# BCN3D_electronics.net
KiCad netlist of a schematic drawn in EAGLE
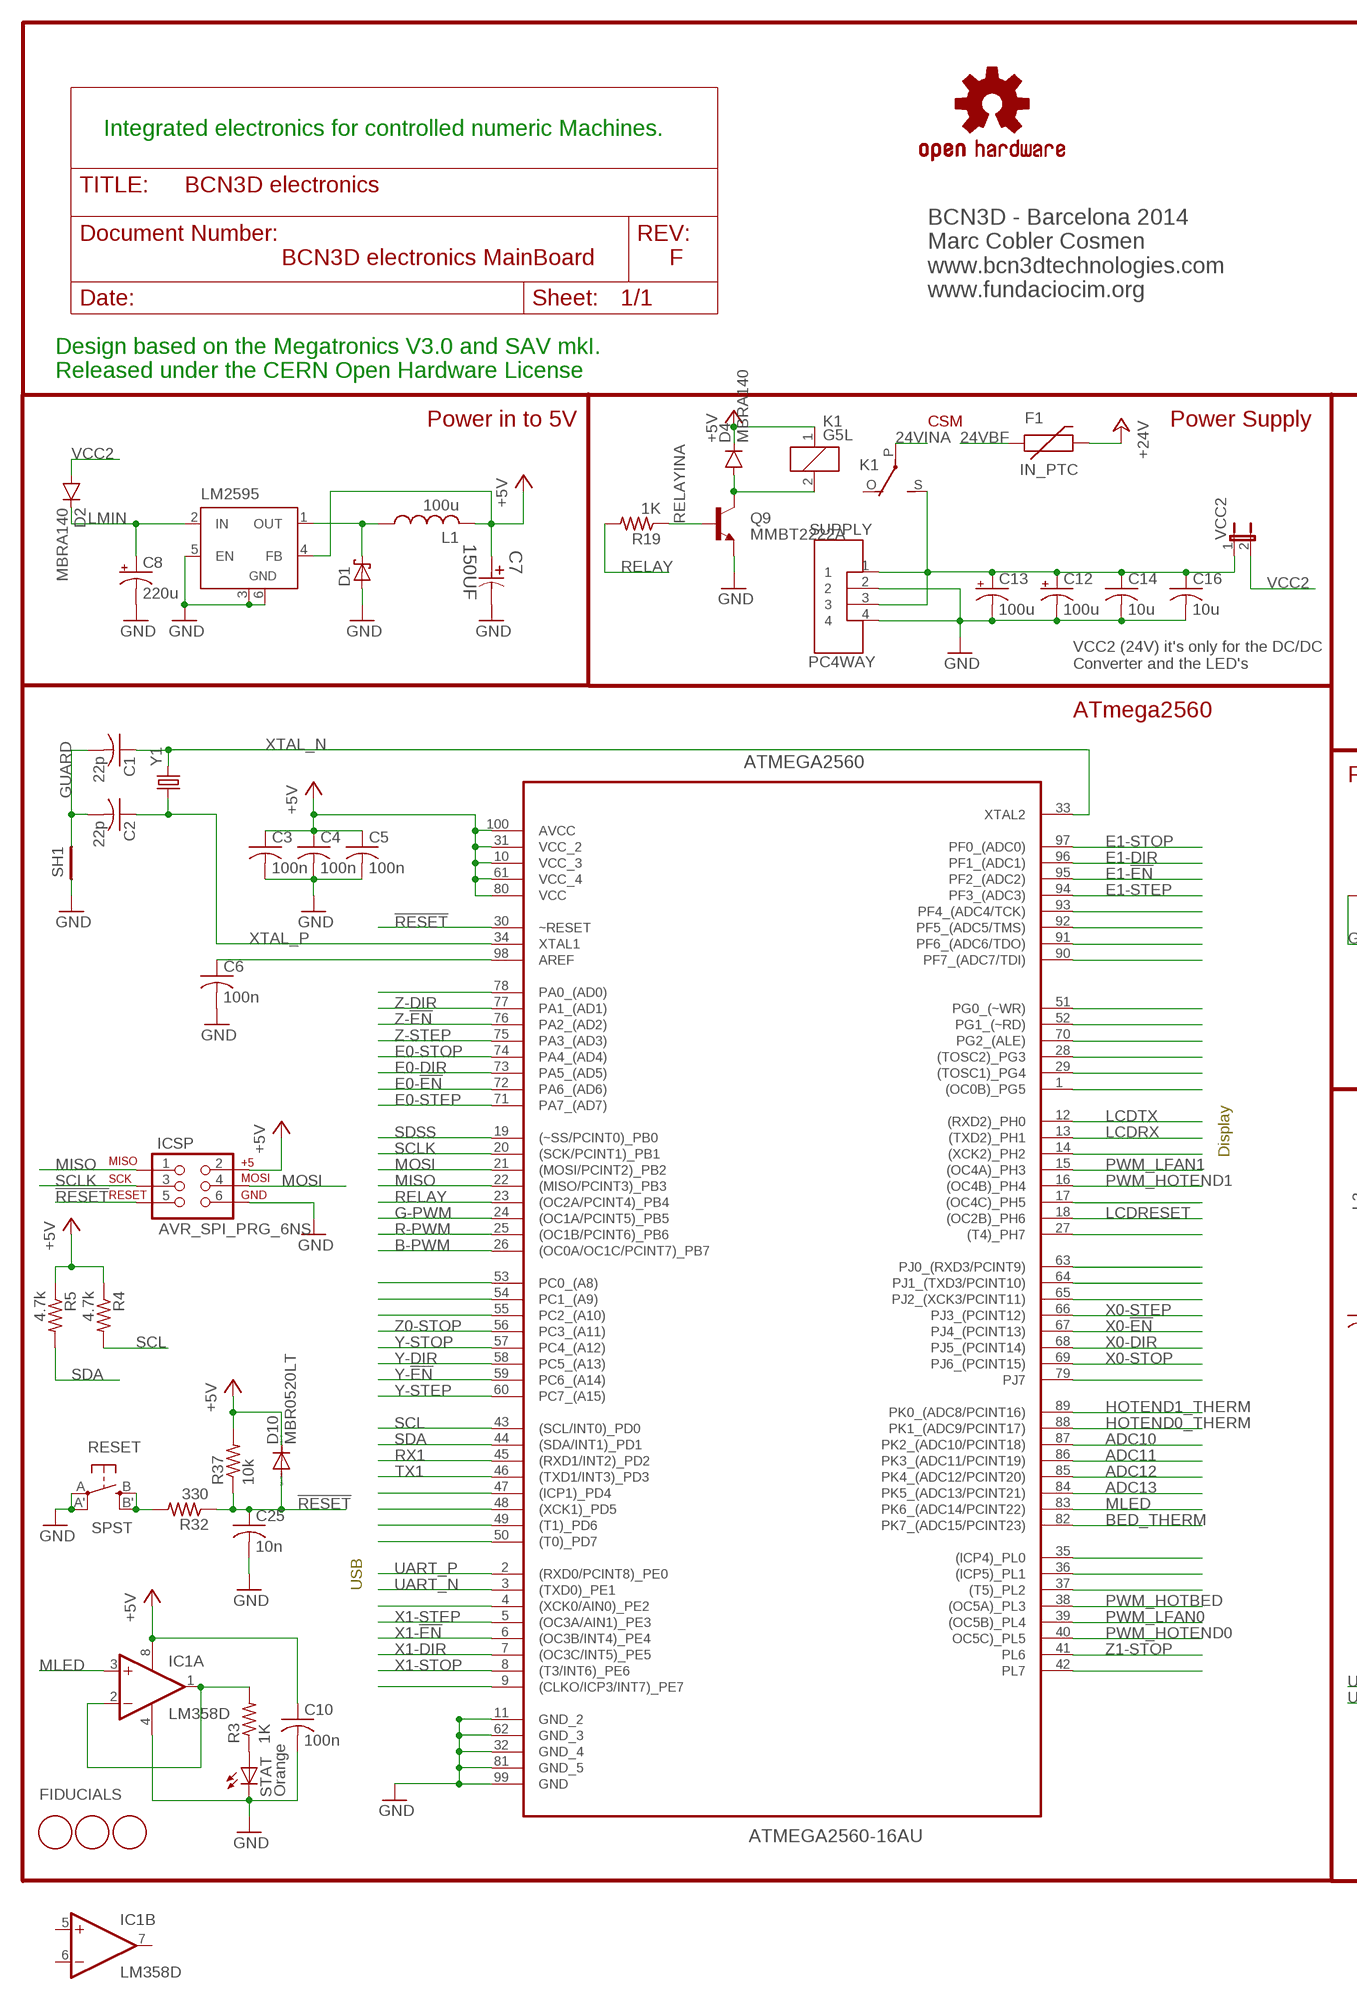
[diagram p0: schematic, sheet 1, part 1 of 2]
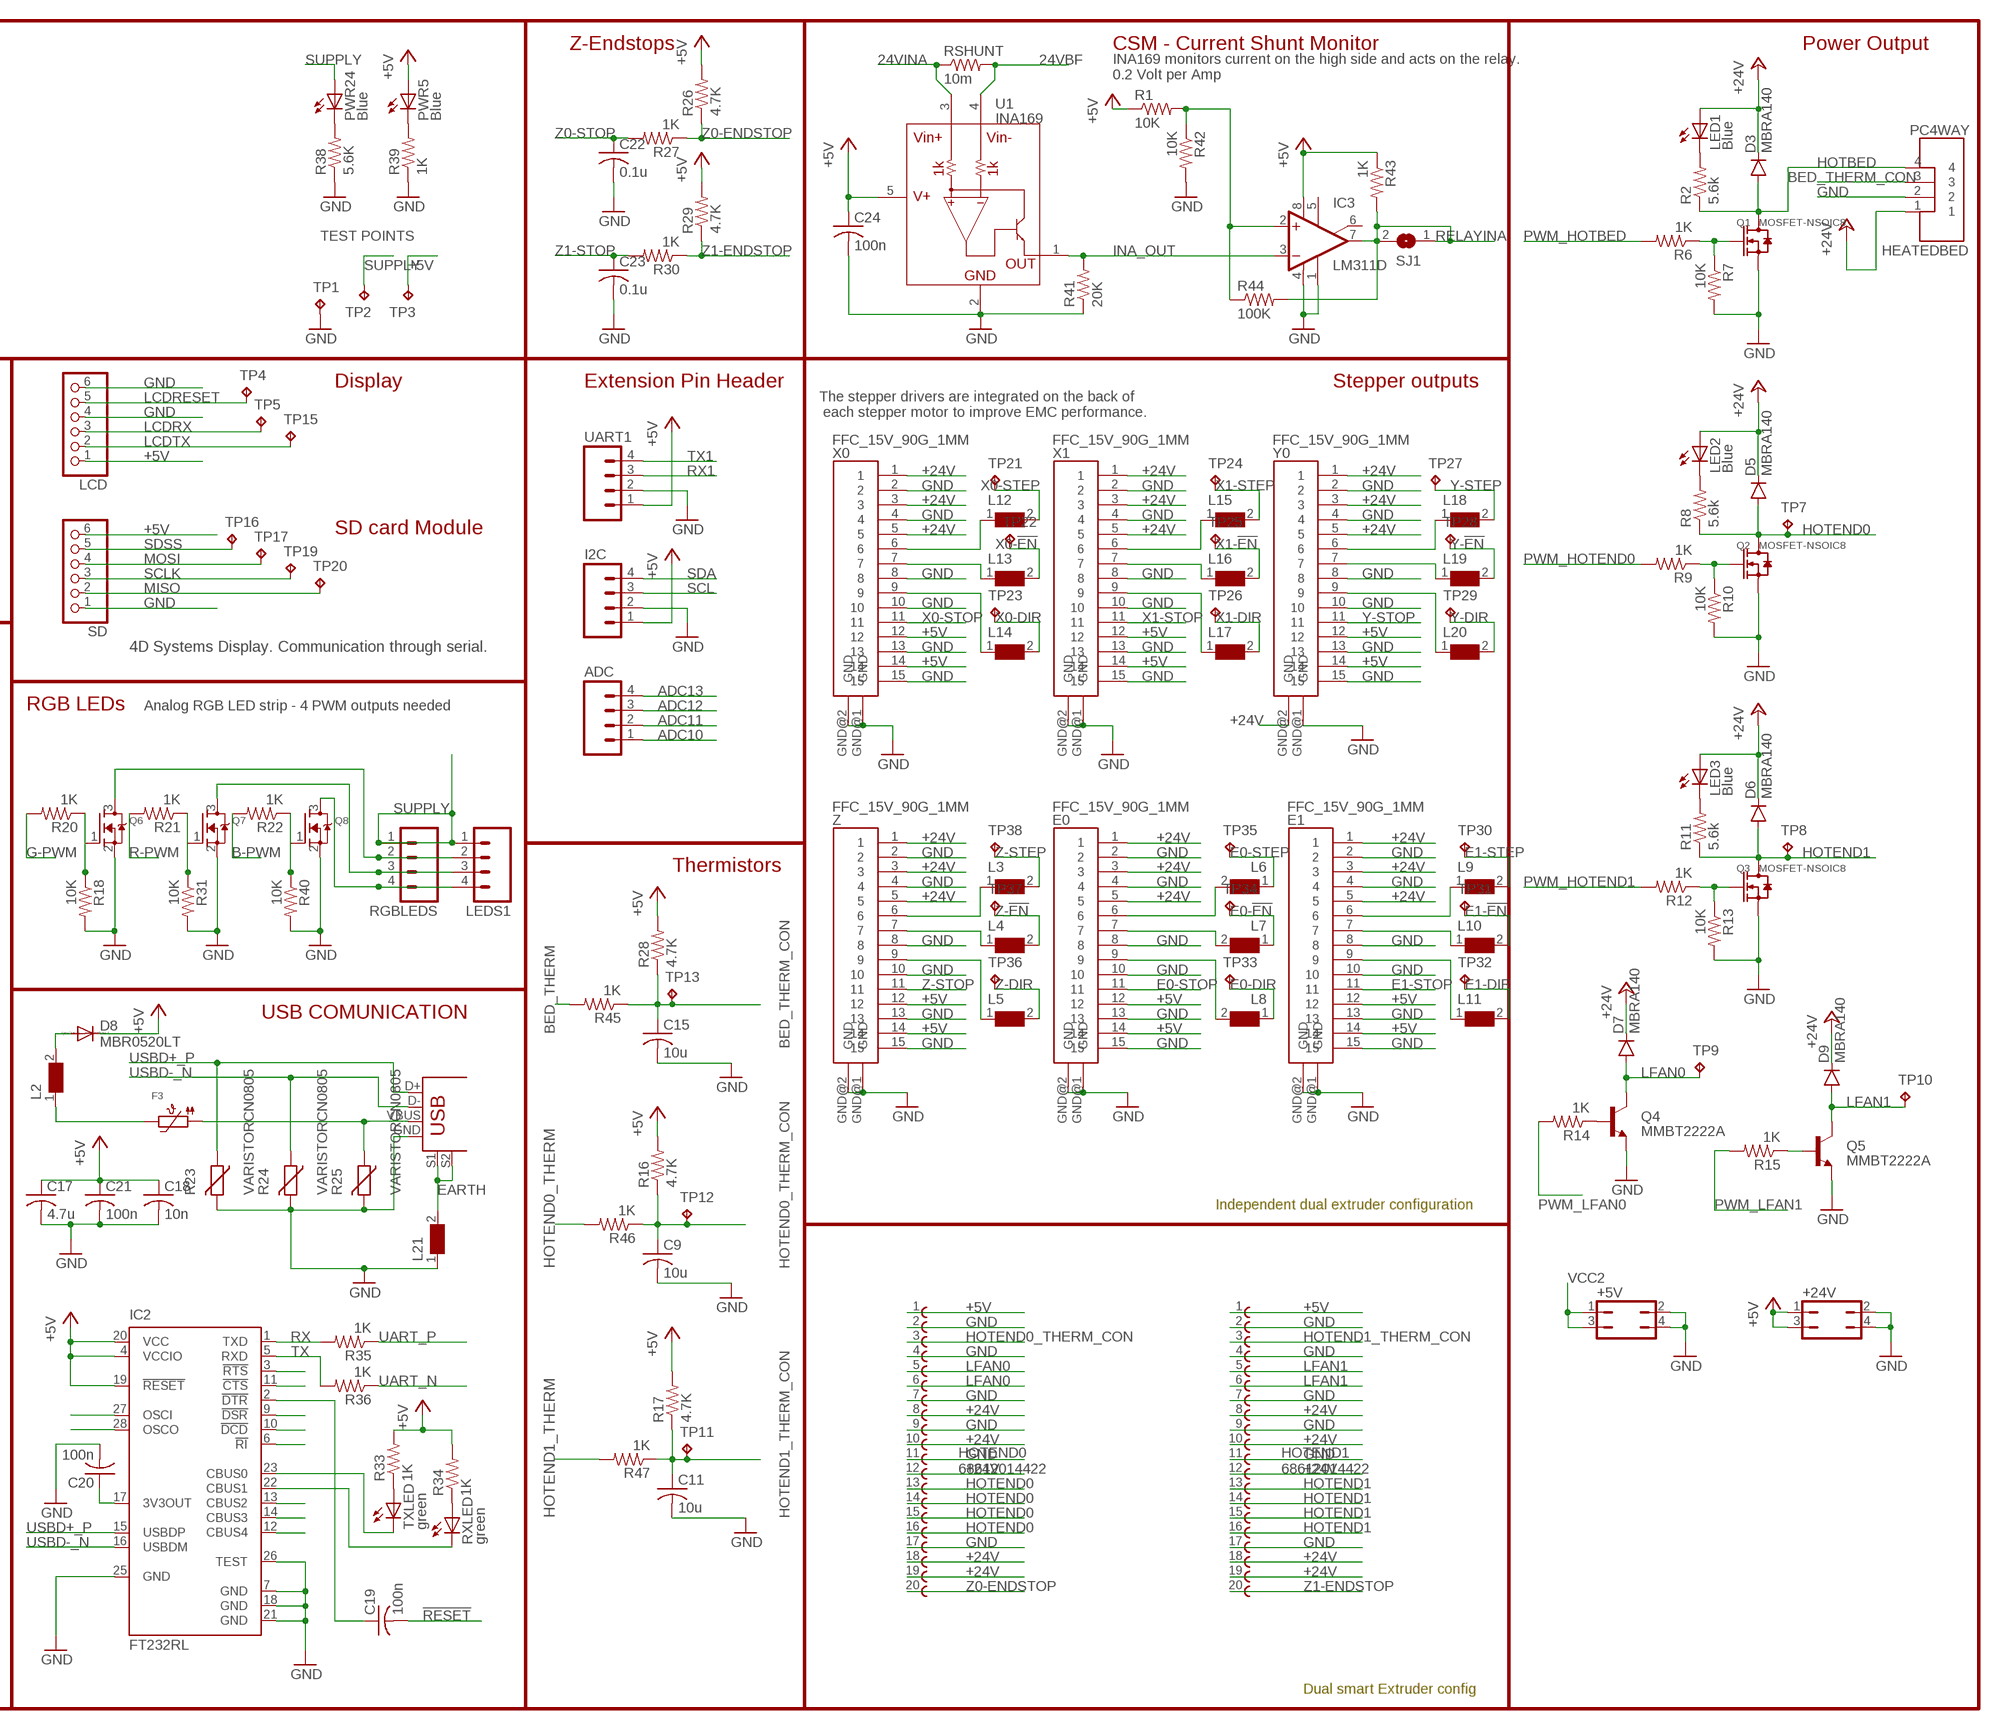
[diagram p1: schematic, sheet 1, part 2 of 2]

(export (version "E")
  (design (tool "Eeschema 10.0.6"))
  (components
    (comp (ref "+5V")
      (value "JP2Q")
      (footprint "eagle-import:JP2Q")
      (libsource (lib "eagle-import") (part "JP2Q"))
    )
    (comp (ref "+24V")
      (value "JP2Q")
      (footprint "eagle-import:JP2Q")
      (libsource (lib "eagle-import") (part "JP2Q"))
    )
    (comp (ref "ADC")
      (value "M04PTH")
      (footprint "eagle-import:1X04")
      (libsource (lib "eagle-import") (part "M04PTH"))
    )
    (comp (ref "ATMEGA2560")
      (value "ATMEGA2560-16AU")
      (footprint "eagle-import:QFP50P1600X1600X120-100N")
      (fields (field (name "MF") "ATMEL"))
      (libsource (lib "eagle-import") (part "ATMEGA2560-16AU"))
    )
    (comp (ref "C1")
      (value "22p")
      (footprint "eagle-import:C0805")
      (fields (field (name "MF") "AVX") (field (name "MPN") "08055A220KAT2A"))
      (libsource (lib "eagle-import") (part "resistor_C-USC0805"))
    )
    (comp (ref "C2")
      (value "22p")
      (footprint "eagle-import:C0805")
      (fields (field (name "MF") "AVX") (field (name "MPN") "08055A220KAT2A"))
      (libsource (lib "eagle-import") (part "resistor_C-USC0805"))
    )
    (comp (ref "C3")
      (value "100n")
      (footprint "eagle-import:C0805")
      (fields (field (name "MF") "AVX") (field (name "MPN") "08055C104KAT2A"))
      (libsource (lib "eagle-import") (part "rcl_C-USC0805"))
    )
    (comp (ref "C4")
      (value "100n")
      (footprint "eagle-import:C0805")
      (fields (field (name "MF") "AVX") (field (name "MPN") "08055C104KAT2A"))
      (libsource (lib "eagle-import") (part "rcl_C-USC0805"))
    )
    (comp (ref "C5")
      (value "100n")
      (footprint "eagle-import:C0805")
      (fields (field (name "MF") "AVX") (field (name "MPN") "08055C104KAT2A"))
      (libsource (lib "eagle-import") (part "rcl_C-USC0805"))
    )
    (comp (ref "C6")
      (value "100n")
      (footprint "eagle-import:C0805")
      (fields (field (name "MF") "AVX") (field (name "MPN") "08055C104KAT2A"))
      (libsource (lib "eagle-import") (part "rcl_C-USC0805"))
    )
    (comp (ref "C7")
      (value "150UF")
      (footprint "eagle-import:CAPAE660X610N")
      (fields
        (field (name "MPN") "EEE-FK0J221P")
        (field (name "TOLERANCE") "±20 %")
        (field (name "MF") "PANASONIC ELECTRONIC COMPONENTS")
        (field (name "MPN_1") "EEEFP1A151AP")
        (field (name "OC_FARNELL") "1539463")
      )
      (libsource (lib "eagle-import") (part "EEE--CASE-DFK0J221P"))
    )
    (comp (ref "C8")
      (value "220u")
      (footprint "eagle-import:UD-8X10_NICHICON")
      (fields (field (name "MF") "PANASONIC ELECTRONIC COMPONENTS") (field (name "MPN") "EEE1VA221UAP"))
      (libsource (lib "eagle-import") (part "CPOL-USUD-8X10"))
    )
    (comp (ref "C9")
      (value "10u")
      (footprint "eagle-import:C0805")
      (fields (field (name "MF") "AVX") (field (name "MPN") "08055C104KAT2A"))
      (libsource (lib "eagle-import") (part "rcl_C-USC0805"))
    )
    (comp (ref "C10")
      (value "100n")
      (footprint "eagle-import:C0805")
      (fields (field (name "MF") "AVX") (field (name "MPN") "08055C104KAT2A"))
      (libsource (lib "eagle-import") (part "rcl_C-USC0805"))
    )
    (comp (ref "C11")
      (value "10u")
      (footprint "eagle-import:C0805")
      (fields (field (name "MF") "AVX") (field (name "MPN") "08055C104KAT2A"))
      (libsource (lib "eagle-import") (part "rcl_C-USC0805"))
    )
    (comp (ref "C12")
      (value "100u")
      (footprint "eagle-import:UD-8X10_NICHICON")
      (fields (field (name "MF") "PANASONIC ELECTRONIC COMPONENTS") (field (name "MPN") "EEEFC1V101AP"))
      (libsource (lib "eagle-import") (part "CPOL-USUD-8X10"))
    )
    (comp (ref "C13")
      (value "100u")
      (footprint "eagle-import:UD-8X10_NICHICON")
      (fields (field (name "MF") "PANASONIC ELECTRONIC COMPONENTS") (field (name "MPN") "EEEFC1V101AP"))
      (libsource (lib "eagle-import") (part "CPOL-USUD-8X10"))
    )
    (comp (ref "C14")
      (value "10u")
      (footprint "eagle-import:C1210K")
      (fields (field (name "MF") "MURATA") (field (name "MPN") "GRM32ER7YA106KA12L"))
      (libsource (lib "eagle-import") (part "rcl_C-USC1210K"))
    )
    (comp (ref "C15")
      (value "10u")
      (footprint "eagle-import:C0805")
      (fields (field (name "MF") "AVX") (field (name "MPN") "08055C104KAT2A"))
      (libsource (lib "eagle-import") (part "rcl_C-USC0805"))
    )
    (comp (ref "C16")
      (value "10u")
      (footprint "eagle-import:C1210K")
      (fields (field (name "MF") "MURATA") (field (name "MPN") "GRM32ER7YA106KA12L"))
      (libsource (lib "eagle-import") (part "rcl_C-USC1210K"))
    )
    (comp (ref "C17")
      (value "4.7u")
      (footprint "eagle-import:C0805")
      (fields (field (name "MF") "AVX") (field (name "MPN") "06035C103JAT2A"))
      (libsource (lib "eagle-import") (part "C-USC0805"))
    )
    (comp (ref "C18")
      (value "10n")
      (footprint "eagle-import:C0805")
      (fields (field (name "MF") "AVX") (field (name "MPN") "08055C103KAT2A"))
      (libsource (lib "eagle-import") (part "C-USC0805"))
    )
    (comp (ref "C19")
      (value "100n")
      (footprint "eagle-import:C0805")
      (fields (field (name "MF") "AVX") (field (name "MPN") "08055C104KAT2A"))
      (libsource (lib "eagle-import") (part "rcl_C-USC0805"))
    )
    (comp (ref "C20")
      (value "100n")
      (footprint "eagle-import:C0805")
      (fields (field (name "MF") "AVX") (field (name "MPN") "08055C104KAT2A"))
      (libsource (lib "eagle-import") (part "rcl_C-USC0805"))
    )
    (comp (ref "C21")
      (value "100n")
      (footprint "eagle-import:C0805")
      (fields (field (name "MF") "AVX") (field (name "MPN") "08055C104KAT2A"))
      (libsource (lib "eagle-import") (part "C-USC0805"))
    )
    (comp (ref "C22")
      (value "0.1u")
      (footprint "eagle-import:C0805")
      (fields (field (name "MF") "AVX") (field (name "MPN") "08055C104KAT2A"))
      (libsource (lib "eagle-import") (part "rcl_C-USC0805"))
    )
    (comp (ref "C23")
      (value "0.1u")
      (footprint "eagle-import:C0805")
      (fields (field (name "MF") "AVX") (field (name "MPN") "08055C104KAT2A"))
      (libsource (lib "eagle-import") (part "rcl_C-USC0805"))
    )
    (comp (ref "C24")
      (value "100n")
      (footprint "eagle-import:C0805")
      (fields (field (name "MF") "AVX") (field (name "MPN") "08055C104KAT2A"))
      (libsource (lib "eagle-import") (part "C-USC0805"))
    )
    (comp (ref "C25")
      (value "10n")
      (footprint "eagle-import:C0805")
      (fields (field (name "MF") "AVX") (field (name "MPN") "08055C103KAT2A"))
      (libsource (lib "eagle-import") (part "rcl_C-USC0805"))
    )
    (comp (ref "D1")
      (value "SCHOTTKY-DIODESMC")
      (footprint "eagle-import:SMC")
      (fields (field (name "MF") "ON SEMICONDUCTOR") (field (name "MPN") "MBRS340T3G"))
      (libsource (lib "eagle-import") (part "SCHOTTKY-DIODESMC"))
    )
    (comp (ref "D2")
      (value "MBRA140")
      (footprint "eagle-import:SMA-DIODE")
      (fields (field (name "MF") "DIODES INC.") (field (name "MPN") "B140-13-F"))
      (libsource (lib "eagle-import") (part "DIODESMA"))
    )
    (comp (ref "D3")
      (value "MBRA140")
      (footprint "eagle-import:SMA-DIODE")
      (fields (field (name "MF") "DIODES INC.") (field (name "MPN") "B140-13-F"))
      (libsource (lib "eagle-import") (part "DIODESMA"))
    )
    (comp (ref "D4")
      (value "MBRA140")
      (footprint "eagle-import:SMA-DIODE")
      (fields (field (name "MF") "DIODES INC.") (field (name "MPN") "B140-13-F"))
      (libsource (lib "eagle-import") (part "DIODESMA"))
    )
    (comp (ref "D5")
      (value "MBRA140")
      (footprint "eagle-import:SMA-DIODE")
      (fields (field (name "MF") "DIODES INC.") (field (name "MPN") "B140-13-F"))
      (libsource (lib "eagle-import") (part "DIODESMA"))
    )
    (comp (ref "D6")
      (value "MBRA140")
      (footprint "eagle-import:SMA-DIODE")
      (fields (field (name "MF") "DIODES INC.") (field (name "MPN") "B140-13-F"))
      (libsource (lib "eagle-import") (part "DIODESMA"))
    )
    (comp (ref "D7")
      (value "MBRA140")
      (footprint "eagle-import:SMA-DIODE")
      (fields (field (name "MF") "DIODES INC.") (field (name "MPN") "B140-13-F"))
      (libsource (lib "eagle-import") (part "DIODESMA"))
    )
    (comp (ref "D8")
      (value "MBR0520LT")
      (footprint "eagle-import:SOD123")
      (fields (field (name "MF") "PANASONIC ELECTRONIC COMPONENTS") (field (name "MPN") "DA22F2100L"))
      (libsource (lib "eagle-import") (part "MBR0520LT"))
    )
    (comp (ref "D9")
      (value "MBRA140")
      (footprint "eagle-import:SMA-DIODE")
      (fields (field (name "MF") "DIODES INC.") (field (name "MPN") "B140-13-F"))
      (libsource (lib "eagle-import") (part "DIODESMA"))
    )
    (comp (ref "D10")
      (value "MBR0520LT")
      (footprint "eagle-import:SOD123")
      (fields (field (name "MF") "PANASONIC ELECTRONIC COMPONENTS") (field (name "MPN") "DA22F2100L"))
      (libsource (lib "eagle-import") (part "MBR0520LT"))
    )
    (comp (ref "E0")
      (value "FFC_15V_90G_1MM")
      (footprint "eagle-import:TE_FFC_CON1MM")
      (libsource (lib "eagle-import") (part "FFC_15V_90G_1MM"))
    )
    (comp (ref "E1")
      (value "FFC_15V_90G_1MM")
      (footprint "eagle-import:TE_FFC_CON1MM")
      (libsource (lib "eagle-import") (part "FFC_15V_90G_1MM"))
    )
    (comp (ref "F1")
      (value "IN_PTC")
      (footprint "eagle-import:PTC-1206")
      (fields (field (name "MF") "SCHURTER") (field (name "MPN") "3413.0329.22"))
      (libsource (lib "eagle-import") (part "PTCSMD"))
    )
    (comp (ref "F3")
      (value "MICROBUILDER_PTC1206_L")
      (footprint "eagle-import:MICROBUILDER_1206_PTC")
      (fields (field (name "MF") "LITTELFUSE") (field (name "MPN") "1206L050YR"))
      (libsource (lib "eagle-import") (part "MICROBUILDER_PTC1206_L"))
    )
    (comp (ref "FID1")
      (value "FIDUCIAL")
      (footprint "eagle-import:FIDUCIAL_1MM")
      (libsource (lib "eagle-import") (part "FIDUCIAL"))
    )
    (comp (ref "FID2")
      (value "FIDUCIAL")
      (footprint "eagle-import:FIDUCIAL_1MM")
      (libsource (lib "eagle-import") (part "FIDUCIAL"))
    )
    (comp (ref "FID3")
      (value "FIDUCIAL")
      (footprint "eagle-import:FIDUCIAL_1MM")
      (libsource (lib "eagle-import") (part "FIDUCIAL"))
    )
    (comp (ref "HEATEDBED")
      (value "PC4WAY")
      (footprint "eagle-import:MOLEX_MINIFIT-JR")
      (fields (field (name "MF") "MOLEX") (field (name "MPN") "39303045"))
      (libsource (lib "eagle-import") (part "POWER_CONNECTOR_4WAY"))
    )
    (comp (ref "HOTEND0")
      (value "68612014422")
      (footprint "eagle-import:68612014422")
      (libsource (lib "eagle-import") (part "68612014422"))
    )
    (comp (ref "HOTEND1")
      (value "68612014422")
      (footprint "eagle-import:68612014422")
      (libsource (lib "eagle-import") (part "68612014422"))
    )
    (comp (ref "I2C")
      (value "M04PTH")
      (footprint "eagle-import:1X04")
      (libsource (lib "eagle-import") (part "M04PTH"))
    )
    (comp (ref "IC1")
      (value "LM358D")
      (footprint "eagle-import:SO08")
      (fields
        (field (name "MF") "STMICROELECTRONICS")
        (field (name "MPN") "LM2904DT")
        (field (name "OC_FARNELL") "1564327")
      )
      (libsource (lib "eagle-import") (part "LM358D"))
    )
    (comp (ref "IC2")
      (value "FT232RL")
      (footprint "eagle-import:SSOP28")
      (fields (field (name "MF") "FTDI"))
      (libsource (lib "eagle-import") (part "FT232RL"))
    )
    (comp (ref "IC3")
      (value "LM311D")
      (footprint "eagle-import:SO08")
      (libsource (lib "eagle-import") (part "LM311D"))
    )
    (comp (ref "ICSP")
      (value "AVR_SPI_PRG_6NS")
      (footprint "eagle-import:2X3-NS")
      (libsource (lib "eagle-import") (part "AVR_SPI_PRG_6NS"))
    )
    (comp (ref "K1")
      (value "G5L")
      (footprint "eagle-import:G5LE")
      (fields
        (field (name "MF") "OMRON ELECTRONIC COMPONENTS")
        (field (name "MPN") "G5LA-1 5DC")
        (field (name "OC_FARNELL") "1455502")
      )
      (libsource (lib "eagle-import") (part "G5L"))
    )
    (comp (ref "L1")
      (value "100u")
      (footprint "eagle-import:SSR1260")
      (fields (field (name "MF") "BOURNS") (field (name "MPN") "SRR1260-101M"))
      (libsource (lib "eagle-import") (part "INDUCTANCE"))
    )
    (comp (ref "L2")
      (value "WE-CBF_0805")
      (footprint "eagle-import:0805")
      (libsource (lib "eagle-import") (part "WE-CBF_0805"))
    )
    (comp (ref "L3")
      (value "WE-CBF_0805")
      (footprint "eagle-import:0805")
      (libsource (lib "eagle-import") (part "WE-CBF_0805"))
    )
    (comp (ref "L4")
      (value "WE-CBF_0805")
      (footprint "eagle-import:0805")
      (libsource (lib "eagle-import") (part "WE-CBF_0805"))
    )
    (comp (ref "L5")
      (value "WE-CBF_0805")
      (footprint "eagle-import:0805")
      (libsource (lib "eagle-import") (part "WE-CBF_0805"))
    )
    (comp (ref "L6")
      (value "WE-CBF_0805")
      (footprint "eagle-import:0805")
      (libsource (lib "eagle-import") (part "WE-CBF_0805"))
    )
    (comp (ref "L7")
      (value "WE-CBF_0805")
      (footprint "eagle-import:0805")
      (libsource (lib "eagle-import") (part "WE-CBF_0805"))
    )
    (comp (ref "L8")
      (value "WE-CBF_0805")
      (footprint "eagle-import:0805")
      (libsource (lib "eagle-import") (part "WE-CBF_0805"))
    )
    (comp (ref "L9")
      (value "WE-CBF_0805")
      (footprint "eagle-import:0805")
      (libsource (lib "eagle-import") (part "WE-CBF_0805"))
    )
    (comp (ref "L10")
      (value "WE-CBF_0805")
      (footprint "eagle-import:0805")
      (libsource (lib "eagle-import") (part "WE-CBF_0805"))
    )
    (comp (ref "L11")
      (value "WE-CBF_0805")
      (footprint "eagle-import:0805")
      (libsource (lib "eagle-import") (part "WE-CBF_0805"))
    )
    (comp (ref "L12")
      (value "WE-CBF_0805")
      (footprint "eagle-import:0805")
      (libsource (lib "eagle-import") (part "WE-CBF_0805"))
    )
    (comp (ref "L13")
      (value "WE-CBF_0805")
      (footprint "eagle-import:0805")
      (libsource (lib "eagle-import") (part "WE-CBF_0805"))
    )
    (comp (ref "L14")
      (value "WE-CBF_0805")
      (footprint "eagle-import:0805")
      (libsource (lib "eagle-import") (part "WE-CBF_0805"))
    )
    (comp (ref "L15")
      (value "WE-CBF_0805")
      (footprint "eagle-import:0805")
      (libsource (lib "eagle-import") (part "WE-CBF_0805"))
    )
    (comp (ref "L16")
      (value "WE-CBF_0805")
      (footprint "eagle-import:0805")
      (libsource (lib "eagle-import") (part "WE-CBF_0805"))
    )
    (comp (ref "L17")
      (value "WE-CBF_0805")
      (footprint "eagle-import:0805")
      (libsource (lib "eagle-import") (part "WE-CBF_0805"))
    )
    (comp (ref "L18")
      (value "WE-CBF_0805")
      (footprint "eagle-import:0805")
      (libsource (lib "eagle-import") (part "WE-CBF_0805"))
    )
    (comp (ref "L19")
      (value "WE-CBF_0805")
      (footprint "eagle-import:0805")
      (libsource (lib "eagle-import") (part "WE-CBF_0805"))
    )
    (comp (ref "L20")
      (value "WE-CBF_0805")
      (footprint "eagle-import:0805")
      (libsource (lib "eagle-import") (part "WE-CBF_0805"))
    )
    (comp (ref "L21")
      (value "WE-CBF_0805")
      (footprint "eagle-import:0805")
      (libsource (lib "eagle-import") (part "WE-CBF_0805"))
    )
    (comp (ref "LCD")
      (value "PINHD-1X6")
      (footprint "eagle-import:1X06")
      (libsource (lib "eagle-import") (part "PINHD-1X6"))
    )
    (comp (ref "LED1")
      (value "Blue")
      (footprint "eagle-import:CHIPLED_0805")
      (fields (field (name "MF") "MULTICOMP") (field (name "MPN") "OVS-0803"))
      (libsource (lib "eagle-import") (part "led_LEDCHIPLED_0805"))
    )
    (comp (ref "LED2")
      (value "Blue")
      (footprint "eagle-import:CHIPLED_0805")
      (fields (field (name "MF") "MULTICOMP") (field (name "MPN") "OVS-0803"))
      (libsource (lib "eagle-import") (part "led_LEDCHIPLED_0805"))
    )
    (comp (ref "LED3")
      (value "Blue")
      (footprint "eagle-import:CHIPLED_0805")
      (fields (field (name "MF") "MULTICOMP") (field (name "MPN") "OVS-0803"))
      (libsource (lib "eagle-import") (part "led_LEDCHIPLED_0805"))
    )
    (comp (ref "LEDS1")
      (value "M04PTH")
      (footprint "eagle-import:1X04")
      (libsource (lib "eagle-import") (part "M04PTH"))
    )
    (comp (ref "LM2595")
      (value "LM2595")
      (footprint "eagle-import:TO263-5")
      (fields (field (name "MF") "TEXAS INSTRUMENTS") (field (name "MPN") "LM2595S-5.0/NOPB"))
      (libsource (lib "eagle-import") (part "LM2595"))
    )
    (comp (ref "LOGO1")
      (value "OSHW-LOGOM")
      (footprint "eagle-import:OSHW-LOGO-M")
      (libsource (lib "eagle-import") (part "OSHW-LOGOM"))
    )
    (comp (ref "PWR5")
      (value "Blue")
      (footprint "eagle-import:CHIPLED_0805")
      (fields (field (name "MF") "MULTICOMP") (field (name "MPN") "OVS-0803"))
      (libsource (lib "eagle-import") (part "led_LEDCHIPLED_0805"))
    )
    (comp (ref "PWR24")
      (value "Blue")
      (footprint "eagle-import:CHIPLED_0805")
      (fields (field (name "MF") "MULTICOMP") (field (name "MPN") "OVS-0803"))
      (libsource (lib "eagle-import") (part "led_LEDCHIPLED_0805"))
    )
    (comp (ref "Q1")
      (value "MOSFET-NSOIC8")
      (footprint "eagle-import:SOIC8")
      (fields (field (name "MF") "INTERNATIONAL RECTIFIER") (field (name "MPN") "IRF8736PBF"))
      (libsource (lib "eagle-import") (part "MOSFET-NSOIC8"))
    )
    (comp (ref "Q2")
      (value "MOSFET-NSOIC8")
      (footprint "eagle-import:SOIC8")
      (fields (field (name "MF") "INTERNATIONAL RECTIFIER") (field (name "MPN") "IRF8736PBF"))
      (libsource (lib "eagle-import") (part "MOSFET-NSOIC8"))
    )
    (comp (ref "Q3")
      (value "MOSFET-NSOIC8")
      (footprint "eagle-import:SOIC8")
      (fields (field (name "MF") "INTERNATIONAL RECTIFIER") (field (name "MPN") "IRF8736PBF"))
      (libsource (lib "eagle-import") (part "MOSFET-NSOIC8"))
    )
    (comp (ref "Q4")
      (value "MMBT2222A")
      (footprint "eagle-import:SOT23-3")
      (fields (field (name "MF") "NXP") (field (name "MPN") "BC817-40"))
      (libsource (lib "eagle-import") (part "TRANSISTOR_NPNMMBT2222A"))
    )
    (comp (ref "Q5")
      (value "MMBT2222A")
      (footprint "eagle-import:SOT23-3")
      (fields (field (name "MF") "NXP") (field (name "MPN") "BC817-40"))
      (libsource (lib "eagle-import") (part "TRANSISTOR_NPNMMBT2222A"))
    )
    (comp (ref "Q6")
      (value "MOSFET-NREFLOW")
      (footprint "eagle-import:SOT23")
      (fields (field (name "MF") "NXP") (field (name "MPN") "BSH103,215"))
      (libsource (lib "eagle-import") (part "MOSFET-NREFLOW"))
    )
    (comp (ref "Q7")
      (value "MOSFET-NREFLOW")
      (footprint "eagle-import:SOT23")
      (fields (field (name "MF") "NXP") (field (name "MPN") "BSH103,215"))
      (libsource (lib "eagle-import") (part "MOSFET-NREFLOW"))
    )
    (comp (ref "Q8")
      (value "MOSFET-NREFLOW")
      (footprint "eagle-import:SOT23")
      (fields (field (name "MF") "NXP") (field (name "MPN") "BSH103,215"))
      (libsource (lib "eagle-import") (part "MOSFET-NREFLOW"))
    )
    (comp (ref "Q9")
      (value "MMBT2222A")
      (footprint "eagle-import:SOT23-3")
      (fields (field (name "MF") "NXP") (field (name "MPN") "BC817-40"))
      (libsource (lib "eagle-import") (part "TRANSISTOR_NPNMMBT2222A"))
    )
    (comp (ref "R1")
      (value "10K")
      (footprint "eagle-import:M0805")
      (fields (field (name "MF") "BOURNS") (field (name "MPN") "CR0805-JW-102ELF"))
      (libsource (lib "eagle-import") (part "rcl_R-US_M0805"))
    )
    (comp (ref "R2")
      (value "5.6k")
      (footprint "eagle-import:M0805")
      (fields (field (name "MF") "BOURNS") (field (name "MPN") "CR0805-JW-102ELF"))
      (libsource (lib "eagle-import") (part "rcl_R-US_M0805"))
    )
    (comp (ref "R3")
      (value "1K")
      (footprint "eagle-import:R0805")
      (fields (field (name "MF") "BOURNS") (field (name "MPN") "CR0805-JW-102ELF"))
      (libsource (lib "eagle-import") (part "rcl_R-US_R0805"))
    )
    (comp (ref "R4")
      (value "4.7k")
      (footprint "eagle-import:M0805")
      (fields (field (name "MF") "BOURNS") (field (name "MPN") "CR0805-JW-103ELF"))
      (libsource (lib "eagle-import") (part "rcl_R-US_M0805"))
    )
    (comp (ref "R5")
      (value "4.7k")
      (footprint "eagle-import:M0805")
      (fields (field (name "MF") "BOURNS") (field (name "MPN") "CR0805-JW-103ELF"))
      (libsource (lib "eagle-import") (part "rcl_R-US_M0805"))
    )
    (comp (ref "R6")
      (value "1K")
      (footprint "eagle-import:M0805")
      (fields (field (name "MF") "BOURNS") (field (name "MPN") "CR0805-JW-102ELF"))
      (libsource (lib "eagle-import") (part "rcl_R-US_M0805"))
    )
    (comp (ref "R7")
      (value "10K")
      (footprint "eagle-import:M0805")
      (fields (field (name "MF") "BOURNS") (field (name "MPN") "CR0805-JW-103ELF"))
      (libsource (lib "eagle-import") (part "rcl_R-US_M0805"))
    )
    (comp (ref "R8")
      (value "5.6k")
      (footprint "eagle-import:M0805")
      (fields (field (name "MF") "BOURNS") (field (name "MPN") "CR0805-JW-102ELF"))
      (libsource (lib "eagle-import") (part "rcl_R-US_M0805"))
    )
    (comp (ref "R9")
      (value "1K")
      (footprint "eagle-import:M0805")
      (fields (field (name "MF") "BOURNS") (field (name "MPN") "CR0805-JW-102ELF"))
      (libsource (lib "eagle-import") (part "rcl_R-US_M0805"))
    )
    (comp (ref "R10")
      (value "10K")
      (footprint "eagle-import:M0805")
      (fields (field (name "MF") "BOURNS") (field (name "MPN") "CR0805-JW-103ELF"))
      (libsource (lib "eagle-import") (part "rcl_R-US_M0805"))
    )
    (comp (ref "R11")
      (value "5.6k")
      (footprint "eagle-import:M0805")
      (fields (field (name "MF") "BOURNS") (field (name "MPN") "CR0805-JW-102ELF"))
      (libsource (lib "eagle-import") (part "rcl_R-US_M0805"))
    )
    (comp (ref "R12")
      (value "1K")
      (footprint "eagle-import:M0805")
      (fields (field (name "MF") "BOURNS") (field (name "MPN") "CR0805-JW-102ELF"))
      (libsource (lib "eagle-import") (part "rcl_R-US_M0805"))
    )
    (comp (ref "R13")
      (value "10K")
      (footprint "eagle-import:M0805")
      (fields (field (name "MF") "BOURNS") (field (name "MPN") "CR0805-JW-103ELF"))
      (libsource (lib "eagle-import") (part "rcl_R-US_M0805"))
    )
    (comp (ref "R14")
      (value "1K")
      (footprint "eagle-import:M0805")
      (fields (field (name "MF") "BOURNS") (field (name "MPN") "CR0805-JW-102ELF"))
      (libsource (lib "eagle-import") (part "rcl_R-US_M0805"))
    )
    (comp (ref "R15")
      (value "1K")
      (footprint "eagle-import:M0805")
      (fields (field (name "MF") "BOURNS") (field (name "MPN") "CR0805-JW-102ELF"))
      (libsource (lib "eagle-import") (part "rcl_R-US_M0805"))
    )
    (comp (ref "R16")
      (value "4.7K")
      (footprint "eagle-import:M0805")
      (fields (field (name "MF") "BOURNS") (field (name "MPN") "CR0805-FX-4701GLF"))
      (libsource (lib "eagle-import") (part "rcl_R-US_M0805"))
    )
    (comp (ref "R17")
      (value "4.7K")
      (footprint "eagle-import:M0805")
      (fields (field (name "MF") "BOURNS") (field (name "MPN") "CR0805-FX-4701GLF"))
      (libsource (lib "eagle-import") (part "rcl_R-US_M0805"))
    )
    (comp (ref "R18")
      (value "10K")
      (footprint "eagle-import:M0805")
      (fields (field (name "MF") "BOURNS") (field (name "MPN") "CR0805-JW-102ELF"))
      (libsource (lib "eagle-import") (part "rcl_R-US_M0805"))
    )
    (comp (ref "R19")
      (value "1K")
      (footprint "eagle-import:M0805")
      (fields (field (name "MF") "BOURNS") (field (name "MPN") "CR0805-JW-102ELF"))
      (libsource (lib "eagle-import") (part "rcl_R-US_M0805"))
    )
    (comp (ref "R20")
      (value "1K")
      (footprint "eagle-import:M0805")
      (fields (field (name "MF") "BOURNS") (field (name "MPN") "CR0805-JW-102ELF"))
      (libsource (lib "eagle-import") (part "rcl_R-US_M0805"))
    )
    (comp (ref "R21")
      (value "1K")
      (footprint "eagle-import:M0805")
      (fields (field (name "MF") "BOURNS") (field (name "MPN") "CR0805-JW-102ELF"))
      (libsource (lib "eagle-import") (part "rcl_R-US_M0805"))
    )
    (comp (ref "R22")
      (value "1K")
      (footprint "eagle-import:M0805")
      (fields (field (name "MF") "BOURNS") (field (name "MPN") "CR0805-JW-102ELF"))
      (libsource (lib "eagle-import") (part "rcl_R-US_M0805"))
    )
    (comp (ref "R23")
      (value "VARISTORCN0805")
      (footprint "eagle-import:CT_CN0805")
      (fields (field (name "MF") "LITTELFUSE") (field (name "MPN") "V5.5MLA0805LH"))
      (libsource (lib "eagle-import") (part "VARISTORCN0805"))
    )
    (comp (ref "R24")
      (value "VARISTORCN0805")
      (footprint "eagle-import:CT_CN0805")
      (fields (field (name "MF") "LITTELFUSE") (field (name "MPN") "V5.5MLA0805LH"))
      (libsource (lib "eagle-import") (part "VARISTORCN0805"))
    )
    (comp (ref "R25")
      (value "VARISTORCN0805")
      (footprint "eagle-import:CT_CN0805")
      (fields (field (name "MF") "LITTELFUSE") (field (name "MPN") "V5.5MLA0805LH"))
      (libsource (lib "eagle-import") (part "VARISTORCN0805"))
    )
    (comp (ref "R26")
      (value "4.7K")
      (footprint "eagle-import:M0805")
      (fields (field (name "MF") "BOURNS") (field (name "MPN") "CR0805-FX-4701GLF"))
      (libsource (lib "eagle-import") (part "rcl_R-US_M0805"))
    )
    (comp (ref "R27")
      (value "1K")
      (footprint "eagle-import:M0805")
      (fields (field (name "MF") "BOURNS") (field (name "MPN") "CR0805-JW-102ELF"))
      (libsource (lib "eagle-import") (part "rcl_R-US_M0805"))
    )
    (comp (ref "R28")
      (value "4.7K")
      (footprint "eagle-import:M0805")
      (fields (field (name "MF") "BOURNS") (field (name "MPN") "CR0805-FX-4701GLF"))
      (libsource (lib "eagle-import") (part "rcl_R-US_M0805"))
    )
    (comp (ref "R29")
      (value "4.7K")
      (footprint "eagle-import:M0805")
      (fields (field (name "MF") "BOURNS") (field (name "MPN") "CR0805-FX-4701GLF"))
      (libsource (lib "eagle-import") (part "rcl_R-US_M0805"))
    )
    (comp (ref "R30")
      (value "1K")
      (footprint "eagle-import:M0805")
      (fields (field (name "MF") "BOURNS") (field (name "MPN") "CR0805-JW-102ELF"))
      (libsource (lib "eagle-import") (part "rcl_R-US_M0805"))
    )
    (comp (ref "R31")
      (value "10K")
      (footprint "eagle-import:M0805")
      (fields (field (name "MF") "BOURNS") (field (name "MPN") "CR0805-JW-102ELF"))
      (libsource (lib "eagle-import") (part "rcl_R-US_M0805"))
    )
    (comp (ref "R32")
      (value "330")
      (footprint "eagle-import:M0805")
      (fields (field (name "MF") "BOURNS") (field (name "MPN") "CR0805-JW-103ELF"))
      (libsource (lib "eagle-import") (part "R-US_M0805"))
    )
    (comp (ref "R33")
      (value "1K")
      (footprint "eagle-import:M0805")
      (fields (field (name "MF") "BOURNS") (field (name "MPN") "CR0805-JW-102ELF"))
      (libsource (lib "eagle-import") (part "rcl_R-US_M0805"))
    )
    (comp (ref "R34")
      (value "1K")
      (footprint "eagle-import:M0805")
      (fields (field (name "MF") "BOURNS") (field (name "MPN") "CR0805-JW-102ELF"))
      (libsource (lib "eagle-import") (part "rcl_R-US_M0805"))
    )
    (comp (ref "R35")
      (value "1K")
      (footprint "eagle-import:M0805")
      (fields (field (name "MF") "BOURNS") (field (name "MPN") "CR0805-JW-102ELF"))
      (libsource (lib "eagle-import") (part "rcl_R-US_M0805"))
    )
    (comp (ref "R36")
      (value "1K")
      (footprint "eagle-import:M0805")
      (fields (field (name "MF") "BOURNS") (field (name "MPN") "CR0805-JW-102ELF"))
      (libsource (lib "eagle-import") (part "rcl_R-US_M0805"))
    )
    (comp (ref "R37")
      (value "10k")
      (footprint "eagle-import:M0805")
      (fields (field (name "MF") "BOURNS") (field (name "MPN") "CR0805-JW-103ELF"))
      (libsource (lib "eagle-import") (part "R-US_M0805"))
    )
    (comp (ref "R38")
      (value "5.6K")
      (footprint "eagle-import:R0805")
      (fields (field (name "MF") "BOURNS") (field (name "MPN") "CR0805-FX-4701GLF"))
      (libsource (lib "eagle-import") (part "rcl_R-US_R0805"))
    )
    (comp (ref "R39")
      (value "1K")
      (footprint "eagle-import:R0805")
      (fields (field (name "MF") "BOURNS") (field (name "MPN") "CR0805-JW-102ELF"))
      (libsource (lib "eagle-import") (part "rcl_R-US_R0805"))
    )
    (comp (ref "R40")
      (value "10K")
      (footprint "eagle-import:M0805")
      (fields (field (name "MF") "BOURNS") (field (name "MPN") "CR0805-JW-102ELF"))
      (libsource (lib "eagle-import") (part "rcl_R-US_M0805"))
    )
    (comp (ref "R41")
      (value "20K")
      (footprint "eagle-import:M0805")
      (fields (field (name "MF") "BOURNS") (field (name "MPN") "CR0805-FX-4701GLF"))
      (libsource (lib "eagle-import") (part "rcl_R-US_M0805"))
    )
    (comp (ref "R42")
      (value "10K")
      (footprint "eagle-import:M0805")
      (fields (field (name "MF") "BOURNS") (field (name "MPN") "CR0805-JW-102ELF"))
      (libsource (lib "eagle-import") (part "rcl_R-US_M0805"))
    )
    (comp (ref "R43")
      (value "1K")
      (footprint "eagle-import:M0805")
      (fields (field (name "MF") "BOURNS") (field (name "MPN") "CR0805-JW-102ELF"))
      (libsource (lib "eagle-import") (part "rcl_R-US_M0805"))
    )
    (comp (ref "R44")
      (value "100K")
      (footprint "eagle-import:M0805")
      (fields (field (name "MF") "BOURNS") (field (name "MPN") "CR0805-JW-102ELF"))
      (libsource (lib "eagle-import") (part "rcl_R-US_M0805"))
    )
    (comp (ref "R45")
      (value "1K")
      (footprint "eagle-import:M0805")
      (fields (field (name "MF") "BOURNS") (field (name "MPN") "CR0805-FX-4701GLF"))
      (libsource (lib "eagle-import") (part "rcl_R-US_M0805"))
    )
    (comp (ref "R46")
      (value "1K")
      (footprint "eagle-import:M0805")
      (fields (field (name "MF") "BOURNS") (field (name "MPN") "CR0805-FX-4701GLF"))
      (libsource (lib "eagle-import") (part "rcl_R-US_M0805"))
    )
    (comp (ref "R47")
      (value "1K")
      (footprint "eagle-import:M0805")
      (fields (field (name "MF") "BOURNS") (field (name "MPN") "CR0805-FX-4701GLF"))
      (libsource (lib "eagle-import") (part "rcl_R-US_M0805"))
    )
    (comp (ref "RESET")
      (value "SPST")
      (footprint "eagle-import:EVQ-Q2")
      (fields (field (name "MF") "PANASONIC ELECTRONIC COMPONENTS") (field (name "MPN") "EVQQ2503W"))
      (libsource (lib "eagle-import") (part "SPST_TACT-EVQQ2"))
    )
    (comp (ref "RGBLEDS")
      (value "M04PTH")
      (footprint "eagle-import:1X04")
      (libsource (lib "eagle-import") (part "M04PTH"))
    )
    (comp (ref "RSHUNT")
      (value "10m")
      (footprint "eagle-import:R2512")
      (libsource (lib "eagle-import") (part "RESISTOR2512"))
    )
    (comp (ref "RXLED")
      (value "green")
      (footprint "eagle-import:CHIPLED_0805")
      (fields (field (name "MF") "WURTH ELEKTRONIK") (field (name "MPN") "150080VS75000"))
      (libsource (lib "eagle-import") (part "led_LEDCHIPLED_0805"))
    )
    (comp (ref "SD")
      (value "PINHD-1X6")
      (footprint "eagle-import:1X06")
      (libsource (lib "eagle-import") (part "PINHD-1X6"))
    )
    (comp (ref "SH1")
      (value "SHORTT5")
      (footprint "eagle-import:SHORT_TOP-50")
      (libsource (lib "eagle-import") (part "SHORTT5"))
    )
    (comp (ref "SJ1") (value "SJ") (footprint "eagle-import:SJ") (libsource (lib "eagle-import") (part "SJ")))
    (comp (ref "STAT")
      (value "Orange")
      (footprint "eagle-import:CHIP-LED0805")
      (fields (field (name "MF") "KINGBRIGHT") (field (name "MPN") "KP-2012SECK"))
      (libsource (lib "eagle-import") (part "LEDCHIP-LED0805"))
    )
    (comp (ref "SUPPLY")
      (value "PC4WAY")
      (footprint "eagle-import:MOLEX_MINIFIT-JR")
      (fields (field (name "MF") "MOLEX") (field (name "MPN") "39303045"))
      (libsource (lib "eagle-import") (part "POWER_CONNECTOR_4WAY"))
    )
    (comp (ref "TP1")
      (value "TPB2,54")
      (footprint "eagle-import:B2,54")
      (libsource (lib "eagle-import") (part "TPB2,54"))
    )
    (comp (ref "TP2")
      (value "TPB2,54")
      (footprint "eagle-import:B2,54")
      (libsource (lib "eagle-import") (part "TPB2,54"))
    )
    (comp (ref "TP3")
      (value "TPB2,54")
      (footprint "eagle-import:B2,54")
      (libsource (lib "eagle-import") (part "TPB2,54"))
    )
    (comp (ref "TP4")
      (value "TPB2,54")
      (footprint "eagle-import:B2,54")
      (libsource (lib "eagle-import") (part "TPB2,54"))
    )
    (comp (ref "TP5")
      (value "TPB2,54")
      (footprint "eagle-import:B2,54")
      (libsource (lib "eagle-import") (part "TPB2,54"))
    )
    (comp (ref "TP7")
      (value "TPB2,54")
      (footprint "eagle-import:B2,54")
      (libsource (lib "eagle-import") (part "TPB2,54"))
    )
    (comp (ref "TP8")
      (value "TPB2,54")
      (footprint "eagle-import:B2,54")
      (libsource (lib "eagle-import") (part "TPB2,54"))
    )
    (comp (ref "TP9")
      (value "TPB2,54")
      (footprint "eagle-import:B2,54")
      (libsource (lib "eagle-import") (part "TPB2,54"))
    )
    (comp (ref "TP10")
      (value "TPB2,54")
      (footprint "eagle-import:B2,54")
      (libsource (lib "eagle-import") (part "TPB2,54"))
    )
    (comp (ref "TP11")
      (value "TPB2,54")
      (footprint "eagle-import:B2,54")
      (libsource (lib "eagle-import") (part "TPB2,54"))
    )
    (comp (ref "TP12")
      (value "TPB2,54")
      (footprint "eagle-import:B2,54")
      (libsource (lib "eagle-import") (part "TPB2,54"))
    )
    (comp (ref "TP13")
      (value "TPB2,54")
      (footprint "eagle-import:B2,54")
      (libsource (lib "eagle-import") (part "TPB2,54"))
    )
    (comp (ref "TP15")
      (value "TPB2,54")
      (footprint "eagle-import:B2,54")
      (libsource (lib "eagle-import") (part "TPB2,54"))
    )
    (comp (ref "TP16")
      (value "TPB2,54")
      (footprint "eagle-import:B2,54")
      (libsource (lib "eagle-import") (part "TPB2,54"))
    )
    (comp (ref "TP17")
      (value "TPB2,54")
      (footprint "eagle-import:B2,54")
      (libsource (lib "eagle-import") (part "TPB2,54"))
    )
    (comp (ref "TP19")
      (value "TPB2,54")
      (footprint "eagle-import:B2,54")
      (libsource (lib "eagle-import") (part "TPB2,54"))
    )
    (comp (ref "TP20")
      (value "TPB2,54")
      (footprint "eagle-import:B2,54")
      (libsource (lib "eagle-import") (part "TPB2,54"))
    )
    (comp (ref "TP21")
      (value "TPB2,54")
      (footprint "eagle-import:B2,54")
      (libsource (lib "eagle-import") (part "TPB2,54"))
    )
    (comp (ref "TP22")
      (value "TPB2,54")
      (footprint "eagle-import:B2,54")
      (libsource (lib "eagle-import") (part "TPB2,54"))
    )
    (comp (ref "TP23")
      (value "TPB2,54")
      (footprint "eagle-import:B2,54")
      (libsource (lib "eagle-import") (part "TPB2,54"))
    )
    (comp (ref "TP24")
      (value "TPB2,54")
      (footprint "eagle-import:B2,54")
      (libsource (lib "eagle-import") (part "TPB2,54"))
    )
    (comp (ref "TP25")
      (value "TPB2,54")
      (footprint "eagle-import:B2,54")
      (libsource (lib "eagle-import") (part "TPB2,54"))
    )
    (comp (ref "TP26")
      (value "TPB2,54")
      (footprint "eagle-import:B2,54")
      (libsource (lib "eagle-import") (part "TPB2,54"))
    )
    (comp (ref "TP27")
      (value "TPB2,54")
      (footprint "eagle-import:B2,54")
      (libsource (lib "eagle-import") (part "TPB2,54"))
    )
    (comp (ref "TP28")
      (value "TPB2,54")
      (footprint "eagle-import:B2,54")
      (libsource (lib "eagle-import") (part "TPB2,54"))
    )
    (comp (ref "TP29")
      (value "TPB2,54")
      (footprint "eagle-import:B2,54")
      (libsource (lib "eagle-import") (part "TPB2,54"))
    )
    (comp (ref "TP30")
      (value "TPB2,54")
      (footprint "eagle-import:B2,54")
      (libsource (lib "eagle-import") (part "TPB2,54"))
    )
    (comp (ref "TP31")
      (value "TPB2,54")
      (footprint "eagle-import:B2,54")
      (libsource (lib "eagle-import") (part "TPB2,54"))
    )
    (comp (ref "TP32")
      (value "TPB2,54")
      (footprint "eagle-import:B2,54")
      (libsource (lib "eagle-import") (part "TPB2,54"))
    )
    (comp (ref "TP33")
      (value "TPB2,54")
      (footprint "eagle-import:B2,54")
      (libsource (lib "eagle-import") (part "TPB2,54"))
    )
    (comp (ref "TP34")
      (value "TPB2,54")
      (footprint "eagle-import:B2,54")
      (libsource (lib "eagle-import") (part "TPB2,54"))
    )
    (comp (ref "TP35")
      (value "TPB2,54")
      (footprint "eagle-import:B2,54")
      (libsource (lib "eagle-import") (part "TPB2,54"))
    )
    (comp (ref "TP36")
      (value "TPB2,54")
      (footprint "eagle-import:B2,54")
      (libsource (lib "eagle-import") (part "TPB2,54"))
    )
    (comp (ref "TP37")
      (value "TPB2,54")
      (footprint "eagle-import:B2,54")
      (libsource (lib "eagle-import") (part "TPB2,54"))
    )
    (comp (ref "TP38")
      (value "TPB2,54")
      (footprint "eagle-import:B2,54")
      (libsource (lib "eagle-import") (part "TPB2,54"))
    )
    (comp (ref "TXLED")
      (value "green")
      (footprint "eagle-import:CHIPLED_0805")
      (fields (field (name "MF") "WURTH ELEKTRONIK") (field (name "MPN") "150080VS75000"))
      (libsource (lib "eagle-import") (part "led_LEDCHIPLED_0805"))
    )
    (comp (ref "U$6")
      (value "USB+SHIELD")
      (footprint "eagle-import:USB-B-PTH")
      (fields (field (name "MF") "MOLEX") (field (name "MPN") "67068-8000"))
      (libsource (lib "eagle-import") (part "USB+SHIELD"))
    )
    (comp (ref "U1")
      (value "INA169")
      (footprint "eagle-import:SOT23-5")
      (libsource (lib "eagle-import") (part "INA169"))
    )
    (comp (ref "UART1")
      (value "M04PTH")
      (footprint "eagle-import:1X04")
      (libsource (lib "eagle-import") (part "M04PTH"))
    )
    (comp (ref "VCC2")
      (value "JP1E")
      (footprint "eagle-import:JP1")
      (libsource (lib "eagle-import") (part "JP1E"))
    )
    (comp (ref "X0")
      (value "FFC_15V_90G_1MM")
      (footprint "eagle-import:TE_FFC_CON1MM")
      (libsource (lib "eagle-import") (part "FFC_15V_90G_1MM"))
    )
    (comp (ref "X1")
      (value "FFC_15V_90G_1MM")
      (footprint "eagle-import:TE_FFC_CON1MM")
      (libsource (lib "eagle-import") (part "FFC_15V_90G_1MM"))
    )
    (comp (ref "Y0")
      (value "FFC_15V_90G_1MM")
      (footprint "eagle-import:TE_FFC_CON1MM")
      (libsource (lib "eagle-import") (part "FFC_15V_90G_1MM"))
    )
    (comp (ref "Y1")
      (value "CRYSTALHC49US")
      (footprint "eagle-import:HC49US")
      (fields (field (name "MF") "TXC") (field (name "MPN") "9B-16.000MAAJ-B"))
      (libsource (lib "eagle-import") (part "CRYSTALHC49US"))
    )
    (comp (ref "Z")
      (value "FFC_15V_90G_1MM")
      (footprint "eagle-import:TE_FFC_CON1MM")
      (libsource (lib "eagle-import") (part "FFC_15V_90G_1MM"))
    )
  )
  (nets
    (net (code "1") (name "+5V") (class "Default")
      (node (ref "+24V") (pin "1") (pinfunction "1_1") (pintype "passive"))
      (node (ref "+24V") (pin "3") (pinfunction "3_3") (pintype "passive"))
      (node (ref "ATMEGA2560") (pin "10") (pinfunction "VCC_3_10") (pintype "power_in"))
      (node (ref "ATMEGA2560") (pin "100") (pinfunction "AVCC_100") (pintype "power_in"))
      (node (ref "ATMEGA2560") (pin "31") (pinfunction "VCC_2_31") (pintype "power_in"))
      (node (ref "ATMEGA2560") (pin "61") (pinfunction "VCC_4_61") (pintype "power_in"))
      (node (ref "ATMEGA2560") (pin "80") (pinfunction "VCC_80") (pintype "power_in"))
      (node (ref "C10") (pin "1") (pinfunction "1_1") (pintype "passive"))
      (node (ref "C17") (pin "1") (pinfunction "1_1") (pintype "passive"))
      (node (ref "C18") (pin "1") (pinfunction "1_1") (pintype "passive"))
      (node (ref "C21") (pin "1") (pinfunction "1_1") (pintype "passive"))
      (node (ref "C24") (pin "1") (pinfunction "1_1") (pintype "passive"))
      (node (ref "C3") (pin "1") (pinfunction "1_1") (pintype "passive"))
      (node (ref "C4") (pin "1") (pinfunction "1_1") (pintype "passive"))
      (node (ref "C5") (pin "1") (pinfunction "1_1") (pintype "passive"))
      (node (ref "C7") (pin "1") (pinfunction "1_1") (pintype "passive"))
      (node (ref "D10") (pin "C") (pinfunction "C_C") (pintype "passive"))
      (node (ref "D4") (pin "C") (pinfunction "C_C") (pintype "passive"))
      (node (ref "D8") (pin "C") (pinfunction "C_C") (pintype "passive"))
      (node (ref "E0") (pin "12") (pinfunction "12_12") (pintype "bidirectional"))
      (node (ref "E0") (pin "14") (pinfunction "14_14") (pintype "bidirectional"))
      (node (ref "E1") (pin "12") (pinfunction "12_12") (pintype "bidirectional"))
      (node (ref "E1") (pin "14") (pinfunction "14_14") (pintype "bidirectional"))
      (node (ref "HOTEND0") (pin "1") (pinfunction "1_1") (pintype "passive"))
      (node (ref "HOTEND1") (pin "1") (pinfunction "1_1") (pintype "passive"))
      (node (ref "I2C") (pin "1") (pinfunction "1_1") (pintype "passive"))
      (node (ref "IC1") (pin "8") (pinfunction "V+_8") (pintype "power_in"))
      (node (ref "IC2") (pin "19") (pinfunction "~{RESET}_19") (pintype "input"))
      (node (ref "IC2") (pin "20") (pinfunction "VCC_20") (pintype "power_in"))
      (node (ref "IC2") (pin "4") (pinfunction "VCCIO_4") (pintype "power_in"))
      (node (ref "IC3") (pin "8") (pinfunction "V+_8") (pintype "power_in"))
      (node (ref "ICSP") (pin "2") (pinfunction "2_2") (pintype "passive"))
      (node (ref "K1") (pin "1") (pinfunction "1_1") (pintype "passive"))
      (node (ref "L1") (pin "B") (pinfunction "2_B") (pintype "passive"))
      (node (ref "LCD") (pin "1") (pinfunction "1_1") (pintype "passive"))
      (node (ref "LM2595") (pin "4") (pinfunction "FB_4") (pintype "input"))
      (node (ref "PWR5") (pin "A") (pinfunction "A_A") (pintype "passive"))
      (node (ref "R1") (pin "1") (pinfunction "1_1") (pintype "passive"))
      (node (ref "R16") (pin "2") (pinfunction "2_2") (pintype "passive"))
      (node (ref "R17") (pin "2") (pinfunction "2_2") (pintype "passive"))
      (node (ref "R26") (pin "2") (pinfunction "2_2") (pintype "passive"))
      (node (ref "R28") (pin "2") (pinfunction "2_2") (pintype "passive"))
      (node (ref "R29") (pin "2") (pinfunction "2_2") (pintype "passive"))
      (node (ref "R33") (pin "2") (pinfunction "2_2") (pintype "passive"))
      (node (ref "R34") (pin "2") (pinfunction "2_2") (pintype "passive"))
      (node (ref "R37") (pin "2") (pinfunction "2_2") (pintype "passive"))
      (node (ref "R4") (pin "1") (pinfunction "1_1") (pintype "passive"))
      (node (ref "R43") (pin "1") (pinfunction "1_1") (pintype "passive"))
      (node (ref "R5") (pin "1") (pinfunction "1_1") (pintype "passive"))
      (node (ref "SD") (pin "6") (pinfunction "6_6") (pintype "passive"))
      (node (ref "TP3") (pin "TP") (pinfunction "TP_TP") (pintype "input"))
      (node (ref "U1") (pin "5") (pinfunction "V+_5") (pintype "bidirectional"))
      (node (ref "UART1") (pin "1") (pinfunction "1_1") (pintype "passive"))
      (node (ref "X0") (pin "12") (pinfunction "12_12") (pintype "bidirectional"))
      (node (ref "X0") (pin "14") (pinfunction "14_14") (pintype "bidirectional"))
      (node (ref "X1") (pin "12") (pinfunction "12_12") (pintype "bidirectional"))
      (node (ref "X1") (pin "14") (pinfunction "14_14") (pintype "bidirectional"))
      (node (ref "Y0") (pin "12") (pinfunction "12_12") (pintype "bidirectional"))
      (node (ref "Y0") (pin "14") (pinfunction "14_14") (pintype "bidirectional"))
      (node (ref "Z") (pin "12") (pinfunction "12_12") (pintype "bidirectional"))
      (node (ref "Z") (pin "14") (pinfunction "14_14") (pintype "bidirectional"))
    )
    (net (code "2") (name "+24V") (class "Default")
      (node (ref "D3") (pin "C") (pinfunction "C_C") (pintype "passive"))
      (node (ref "D5") (pin "C") (pinfunction "C_C") (pintype "passive"))
      (node (ref "D6") (pin "C") (pinfunction "C_C") (pintype "passive"))
      (node (ref "D7") (pin "C") (pinfunction "C_C") (pintype "passive"))
      (node (ref "D9") (pin "C") (pinfunction "C_C") (pintype "passive"))
      (node (ref "E0") (pin "1") (pinfunction "1_1") (pintype "bidirectional"))
      (node (ref "E0") (pin "3") (pinfunction "3_3") (pintype "bidirectional"))
      (node (ref "E0") (pin "5") (pinfunction "5_5") (pintype "bidirectional"))
      (node (ref "E1") (pin "1") (pinfunction "1_1") (pintype "bidirectional"))
      (node (ref "E1") (pin "3") (pinfunction "3_3") (pintype "bidirectional"))
      (node (ref "E1") (pin "5") (pinfunction "5_5") (pintype "bidirectional"))
      (node (ref "F1") (pin "2") (pinfunction "2_2") (pintype "bidirectional"))
      (node (ref "HEATEDBED") (pin "1") (pinfunction "1_1") (pintype "bidirectional"))
      (node (ref "HOTEND0") (pin "10") (pinfunction "10_10") (pintype "passive"))
      (node (ref "HOTEND0") (pin "12") (pinfunction "12_12") (pintype "passive"))
      (node (ref "HOTEND0") (pin "18") (pinfunction "18_18") (pintype "passive"))
      (node (ref "HOTEND0") (pin "19") (pinfunction "19_19") (pintype "passive"))
      (node (ref "HOTEND0") (pin "8") (pinfunction "8_8") (pintype "passive"))
      (node (ref "HOTEND1") (pin "10") (pinfunction "10_10") (pintype "passive"))
      (node (ref "HOTEND1") (pin "12") (pinfunction "12_12") (pintype "passive"))
      (node (ref "HOTEND1") (pin "18") (pinfunction "18_18") (pintype "passive"))
      (node (ref "HOTEND1") (pin "19") (pinfunction "19_19") (pintype "passive"))
      (node (ref "HOTEND1") (pin "8") (pinfunction "8_8") (pintype "passive"))
      (node (ref "LED1") (pin "A") (pinfunction "A_A") (pintype "passive"))
      (node (ref "LED2") (pin "A") (pinfunction "A_A") (pintype "passive"))
      (node (ref "LED3") (pin "A") (pinfunction "A_A") (pintype "passive"))
      (node (ref "X0") (pin "1") (pinfunction "1_1") (pintype "bidirectional"))
      (node (ref "X0") (pin "3") (pinfunction "3_3") (pintype "bidirectional"))
      (node (ref "X0") (pin "5") (pinfunction "5_5") (pintype "bidirectional"))
      (node (ref "X1") (pin "1") (pinfunction "1_1") (pintype "bidirectional"))
      (node (ref "X1") (pin "3") (pinfunction "3_3") (pintype "bidirectional"))
      (node (ref "X1") (pin "5") (pinfunction "5_5") (pintype "bidirectional"))
      (node (ref "Y0") (pin "1") (pinfunction "1_1") (pintype "bidirectional"))
      (node (ref "Y0") (pin "3") (pinfunction "3_3") (pintype "bidirectional"))
      (node (ref "Y0") (pin "5") (pinfunction "5_5") (pintype "bidirectional"))
      (node (ref "Y0") (pin "GND@2") (pinfunction "GND_GND@2") (pintype "bidirectional"))
      (node (ref "Z") (pin "1") (pinfunction "1_1") (pintype "bidirectional"))
      (node (ref "Z") (pin "3") (pinfunction "3_3") (pintype "bidirectional"))
      (node (ref "Z") (pin "5") (pinfunction "5_5") (pintype "bidirectional"))
    )
    (net (code "3") (name "/24VBF") (class "Default")
      (node (ref "F1") (pin "1") (pinfunction "1_1") (pintype "bidirectional"))
      (node (ref "RSHUNT") (pin "2") (pinfunction "2_2") (pintype "passive"))
      (node (ref "U1") (pin "4") (pinfunction "VIN-_4") (pintype "bidirectional"))
    )
    (net (code "4") (name "/24VINA") (class "Default")
      (node (ref "K1") (pin "P") (pinfunction "P_P") (pintype "passive"))
      (node (ref "RSHUNT") (pin "1") (pinfunction "1_1") (pintype "passive"))
      (node (ref "U1") (pin "3") (pinfunction "VIN+_3") (pintype "bidirectional"))
    )
    (net (code "5") (name "/ADC10") (class "Default")
      (node (ref "ADC") (pin "1") (pinfunction "1_1") (pintype "passive"))
      (node (ref "ATMEGA2560") (pin "87") (pinfunction "PK2_(ADC10/PCINT18)_87") (pintype "bidirectional"))
    )
    (net (code "6") (name "/ADC11") (class "Default")
      (node (ref "ADC") (pin "2") (pinfunction "2_2") (pintype "passive"))
      (node (ref "ATMEGA2560") (pin "86") (pinfunction "PK3_(ADC11/PCINT19)_86") (pintype "bidirectional"))
    )
    (net (code "7") (name "/ADC12") (class "Default")
      (node (ref "ADC") (pin "3") (pinfunction "3_3") (pintype "passive"))
      (node (ref "ATMEGA2560") (pin "85") (pinfunction "PK4_(ADC12/PCINT20)_85") (pintype "bidirectional"))
    )
    (net (code "8") (name "/ADC13") (class "Default")
      (node (ref "ADC") (pin "4") (pinfunction "4_4") (pintype "passive"))
      (node (ref "ATMEGA2560") (pin "84") (pinfunction "PK5_(ADC13/PCINT21)_84") (pintype "bidirectional"))
    )
    (net (code "9") (name "/B-PWM") (class "Default")
      (node (ref "ATMEGA2560") (pin "26") (pinfunction "(OC0A/OC1C/PCINT7)_PB7_26") (pintype "bidirectional"))
      (node (ref "R22") (pin "2") (pinfunction "2_2") (pintype "passive"))
    )
    (net (code "10") (name "/BED_THERM") (class "Default")
      (node (ref "ATMEGA2560") (pin "82") (pinfunction "PK7_(ADC15/PCINT23)_82") (pintype "bidirectional"))
      (node (ref "R45") (pin "2") (pinfunction "2_2") (pintype "passive"))
    )
    (net (code "11") (name "/BED_THERM_CON") (class "Default")
      (node (ref "C15") (pin "1") (pinfunction "1_1") (pintype "passive"))
      (node (ref "HEATEDBED") (pin "3") (pinfunction "3_3") (pintype "bidirectional"))
      (node (ref "R28") (pin "1") (pinfunction "1_1") (pintype "passive"))
      (node (ref "R45") (pin "1") (pinfunction "1_1") (pintype "passive"))
      (node (ref "TP13") (pin "TP") (pinfunction "TP_TP") (pintype "input"))
    )
    (net (code "12") (name "/E0-DIR") (class "Default")
      (node (ref "ATMEGA2560") (pin "73") (pinfunction "PA5_(AD5)_73") (pintype "bidirectional"))
      (node (ref "L8") (pin "1") (pinfunction "1_1") (pintype "passive"))
      (node (ref "TP33") (pin "TP") (pinfunction "TP_TP") (pintype "input"))
    )
    (net (code "13") (name "/E0-STEP") (class "Default")
      (node (ref "ATMEGA2560") (pin "71") (pinfunction "PA7_(AD7)_71") (pintype "bidirectional"))
      (node (ref "L6") (pin "1") (pinfunction "1_1") (pintype "passive"))
      (node (ref "TP35") (pin "TP") (pinfunction "TP_TP") (pintype "input"))
    )
    (net (code "14") (name "/E0-STOP") (class "Default")
      (node (ref "ATMEGA2560") (pin "74") (pinfunction "PA4_(AD4)_74") (pintype "bidirectional"))
      (node (ref "E0") (pin "11") (pinfunction "11_11") (pintype "bidirectional"))
    )
    (net (code "15") (name "/E0-~{EN}") (class "Default")
      (node (ref "ATMEGA2560") (pin "72") (pinfunction "PA6_(AD6)_72") (pintype "bidirectional"))
      (node (ref "L7") (pin "1") (pinfunction "1_1") (pintype "passive"))
      (node (ref "TP34") (pin "TP") (pinfunction "TP_TP") (pintype "input"))
    )
    (net (code "16") (name "/E1-DIR") (class "Default")
      (node (ref "ATMEGA2560") (pin "96") (pinfunction "PF1_(ADC1)_96") (pintype "bidirectional"))
      (node (ref "L11") (pin "2") (pinfunction "2_2") (pintype "passive"))
      (node (ref "TP32") (pin "TP") (pinfunction "TP_TP") (pintype "input"))
    )
    (net (code "17") (name "/E1-STEP") (class "Default")
      (node (ref "ATMEGA2560") (pin "94") (pinfunction "PF3_(ADC3)_94") (pintype "bidirectional"))
      (node (ref "L9") (pin "2") (pinfunction "2_2") (pintype "passive"))
      (node (ref "TP30") (pin "TP") (pinfunction "TP_TP") (pintype "input"))
    )
    (net (code "18") (name "/E1-STOP") (class "Default")
      (node (ref "ATMEGA2560") (pin "97") (pinfunction "PF0_(ADC0)_97") (pintype "bidirectional"))
      (node (ref "E1") (pin "11") (pinfunction "11_11") (pintype "bidirectional"))
    )
    (net (code "19") (name "/E1-~{EN}") (class "Default")
      (node (ref "ATMEGA2560") (pin "95") (pinfunction "PF2_(ADC2)_95") (pintype "bidirectional"))
      (node (ref "L10") (pin "2") (pinfunction "2_2") (pintype "passive"))
      (node (ref "TP31") (pin "TP") (pinfunction "TP_TP") (pintype "input"))
    )
    (net (code "20") (name "/EARTH") (class "Default")
      (node (ref "L21") (pin "2") (pinfunction "2_2") (pintype "passive"))
      (node (ref "U$6") (pin "S1") (pinfunction "S1_S1") (pintype "bidirectional"))
      (node (ref "U$6") (pin "S2") (pinfunction "S2_S2") (pintype "bidirectional"))
    )
    (net (code "21") (name "/G-PWM") (class "Default")
      (node (ref "ATMEGA2560") (pin "24") (pinfunction "(OC1A/PCINT5)_PB5_24") (pintype "bidirectional"))
      (node (ref "R20") (pin "2") (pinfunction "2_2") (pintype "passive"))
    )
    (net (code "22") (name "/GUARD") (class "Default")
      (node (ref "C1") (pin "2") (pinfunction "2_2") (pintype "passive"))
      (node (ref "C2") (pin "2") (pinfunction "2_2") (pintype "passive"))
      (node (ref "SH1") (pin "2") (pinfunction "P$2_2") (pintype "bidirectional"))
    )
    (net (code "23") (name "/HOTBED") (class "Default")
      (node (ref "D3") (pin "A") (pinfunction "A_A") (pintype "passive"))
      (node (ref "HEATEDBED") (pin "4") (pinfunction "4_4") (pintype "bidirectional"))
      (node (ref "Q1") (pin "5") (pinfunction "D_5") (pintype "passive"))
      (node (ref "Q1") (pin "6") (pinfunction "D_6") (pintype "passive"))
      (node (ref "Q1") (pin "7") (pinfunction "D_7") (pintype "passive"))
      (node (ref "Q1") (pin "8") (pinfunction "D_8") (pintype "passive"))
      (node (ref "R2") (pin "1") (pinfunction "1_1") (pintype "passive"))
    )
    (net (code "24") (name "/HOTEND0") (class "Default")
      (node (ref "D5") (pin "A") (pinfunction "A_A") (pintype "passive"))
      (node (ref "HOTEND0") (pin "13") (pinfunction "13_13") (pintype "passive"))
      (node (ref "HOTEND0") (pin "14") (pinfunction "14_14") (pintype "passive"))
      (node (ref "HOTEND0") (pin "15") (pinfunction "15_15") (pintype "passive"))
      (node (ref "HOTEND0") (pin "16") (pinfunction "16_16") (pintype "passive"))
      (node (ref "Q2") (pin "5") (pinfunction "D_5") (pintype "passive"))
      (node (ref "Q2") (pin "6") (pinfunction "D_6") (pintype "passive"))
      (node (ref "Q2") (pin "7") (pinfunction "D_7") (pintype "passive"))
      (node (ref "Q2") (pin "8") (pinfunction "D_8") (pintype "passive"))
      (node (ref "R8") (pin "1") (pinfunction "1_1") (pintype "passive"))
      (node (ref "TP7") (pin "TP") (pinfunction "TP_TP") (pintype "input"))
    )
    (net (code "25") (name "/HOTEND0_THERM") (class "Default")
      (node (ref "ATMEGA2560") (pin "88") (pinfunction "PK1_(ADC9/PCINT17)_88") (pintype "bidirectional"))
      (node (ref "R46") (pin "2") (pinfunction "2_2") (pintype "passive"))
    )
    (net (code "26") (name "/HOTEND0_THERM_CON") (class "Default")
      (node (ref "C9") (pin "1") (pinfunction "1_1") (pintype "passive"))
      (node (ref "HOTEND0") (pin "3") (pinfunction "3_3") (pintype "passive"))
      (node (ref "R16") (pin "1") (pinfunction "1_1") (pintype "passive"))
      (node (ref "R46") (pin "1") (pinfunction "1_1") (pintype "passive"))
      (node (ref "TP12") (pin "TP") (pinfunction "TP_TP") (pintype "input"))
    )
    (net (code "27") (name "/HOTEND1") (class "Default")
      (node (ref "D6") (pin "A") (pinfunction "A_A") (pintype "passive"))
      (node (ref "HOTEND1") (pin "13") (pinfunction "13_13") (pintype "passive"))
      (node (ref "HOTEND1") (pin "14") (pinfunction "14_14") (pintype "passive"))
      (node (ref "HOTEND1") (pin "15") (pinfunction "15_15") (pintype "passive"))
      (node (ref "HOTEND1") (pin "16") (pinfunction "16_16") (pintype "passive"))
      (node (ref "Q3") (pin "5") (pinfunction "D_5") (pintype "passive"))
      (node (ref "Q3") (pin "6") (pinfunction "D_6") (pintype "passive"))
      (node (ref "Q3") (pin "7") (pinfunction "D_7") (pintype "passive"))
      (node (ref "Q3") (pin "8") (pinfunction "D_8") (pintype "passive"))
      (node (ref "R11") (pin "1") (pinfunction "1_1") (pintype "passive"))
      (node (ref "TP8") (pin "TP") (pinfunction "TP_TP") (pintype "input"))
    )
    (net (code "28") (name "/HOTEND1_THERM") (class "Default")
      (node (ref "ATMEGA2560") (pin "89") (pinfunction "PK0_(ADC8/PCINT16)_89") (pintype "bidirectional"))
      (node (ref "R47") (pin "2") (pinfunction "2_2") (pintype "passive"))
    )
    (net (code "29") (name "/HOTEND1_THERM_CON") (class "Default")
      (node (ref "C11") (pin "1") (pinfunction "1_1") (pintype "passive"))
      (node (ref "HOTEND1") (pin "3") (pinfunction "3_3") (pintype "passive"))
      (node (ref "R17") (pin "1") (pinfunction "1_1") (pintype "passive"))
      (node (ref "R47") (pin "1") (pinfunction "1_1") (pintype "passive"))
      (node (ref "TP11") (pin "TP") (pinfunction "TP_TP") (pintype "input"))
    )
    (net (code "30") (name "/INA_OUT") (class "Default")
      (node (ref "IC3") (pin "3") (pinfunction "-IN_3") (pintype "input"))
      (node (ref "R41") (pin "2") (pinfunction "2_2") (pintype "passive"))
      (node (ref "U1") (pin "1") (pinfunction "OUT_1") (pintype "bidirectional"))
    )
    (net (code "31") (name "/LCDRESET") (class "Default")
      (node (ref "ATMEGA2560") (pin "18") (pinfunction "(OC2B)_PH6_18") (pintype "bidirectional"))
      (node (ref "LCD") (pin "5") (pinfunction "5_5") (pintype "passive"))
      (node (ref "TP4") (pin "TP") (pinfunction "TP_TP") (pintype "input"))
    )
    (net (code "32") (name "/LCDRX") (class "Default")
      (node (ref "ATMEGA2560") (pin "13") (pinfunction "(TXD2)_PH1_13") (pintype "bidirectional"))
      (node (ref "LCD") (pin "3") (pinfunction "3_3") (pintype "passive"))
      (node (ref "TP5") (pin "TP") (pinfunction "TP_TP") (pintype "input"))
    )
    (net (code "33") (name "/LCDTX") (class "Default")
      (node (ref "ATMEGA2560") (pin "12") (pinfunction "(RXD2)_PH0_12") (pintype "bidirectional"))
      (node (ref "LCD") (pin "2") (pinfunction "2_2") (pintype "passive"))
      (node (ref "TP15") (pin "TP") (pinfunction "TP_TP") (pintype "input"))
    )
    (net (code "34") (name "/LFAN0") (class "Default")
      (node (ref "D7") (pin "A") (pinfunction "A_A") (pintype "passive"))
      (node (ref "HOTEND0") (pin "5") (pinfunction "5_5") (pintype "passive"))
      (node (ref "HOTEND0") (pin "6") (pinfunction "6_6") (pintype "passive"))
      (node (ref "Q4") (pin "3") (pinfunction "C_3") (pintype "passive"))
      (node (ref "TP9") (pin "TP") (pinfunction "TP_TP") (pintype "input"))
    )
    (net (code "35") (name "/LFAN1") (class "Default")
      (node (ref "D9") (pin "A") (pinfunction "A_A") (pintype "passive"))
      (node (ref "HOTEND1") (pin "5") (pinfunction "5_5") (pintype "passive"))
      (node (ref "HOTEND1") (pin "6") (pinfunction "6_6") (pintype "passive"))
      (node (ref "Q5") (pin "3") (pinfunction "C_3") (pintype "passive"))
      (node (ref "TP10") (pin "TP") (pinfunction "TP_TP") (pintype "input"))
    )
    (net (code "36") (name "/LMIN") (class "Default")
      (node (ref "C8") (pin "+") (pinfunction "+_+") (pintype "passive"))
      (node (ref "D2") (pin "C") (pinfunction "C_C") (pintype "passive"))
      (node (ref "LM2595") (pin "2") (pinfunction "IN_2") (pintype "input"))
    )
    (net (code "37") (name "/MISO") (class "Default")
      (node (ref "ATMEGA2560") (pin "22") (pinfunction "(MISO/PCINT3)_PB3_22") (pintype "bidirectional"))
      (node (ref "ICSP") (pin "1") (pinfunction "1_1") (pintype "passive"))
      (node (ref "SD") (pin "2") (pinfunction "2_2") (pintype "passive"))
      (node (ref "TP20") (pin "TP") (pinfunction "TP_TP") (pintype "input"))
    )
    (net (code "38") (name "/MLED") (class "Default")
      (node (ref "ATMEGA2560") (pin "83") (pinfunction "PK6_(ADC14/PCINT22)_83") (pintype "bidirectional"))
      (node (ref "IC1") (pin "3") (pinfunction "+IN_3") (pintype "input"))
    )
    (net (code "39") (name "/MOSI") (class "Default")
      (node (ref "ATMEGA2560") (pin "21") (pinfunction "(MOSI/PCINT2)_PB2_21") (pintype "bidirectional"))
      (node (ref "ICSP") (pin "4") (pinfunction "4_4") (pintype "passive"))
      (node (ref "SD") (pin "4") (pinfunction "4_4") (pintype "passive"))
      (node (ref "TP17") (pin "TP") (pinfunction "TP_TP") (pintype "input"))
    )
    (net (code "40") (name "/PWM_HOTBED") (class "Default")
      (node (ref "ATMEGA2560") (pin "38") (pinfunction "(OC5A)_PL3_38") (pintype "bidirectional"))
      (node (ref "R6") (pin "2") (pinfunction "2_2") (pintype "passive"))
    )
    (net (code "41") (name "/PWM_HOTEND0") (class "Default")
      (node (ref "ATMEGA2560") (pin "40") (pinfunction "OC5C)_PL5_40") (pintype "bidirectional"))
      (node (ref "R9") (pin "2") (pinfunction "2_2") (pintype "passive"))
    )
    (net (code "42") (name "/PWM_HOTEND1") (class "Default")
      (node (ref "ATMEGA2560") (pin "16") (pinfunction "(OC4B)_PH4_16") (pintype "bidirectional"))
      (node (ref "R12") (pin "2") (pinfunction "2_2") (pintype "passive"))
    )
    (net (code "43") (name "/PWM_LFAN0") (class "Default")
      (node (ref "ATMEGA2560") (pin "39") (pinfunction "(OC5B)_PL4_39") (pintype "bidirectional"))
      (node (ref "R14") (pin "2") (pinfunction "2_2") (pintype "passive"))
    )
    (net (code "44") (name "/PWM_LFAN1") (class "Default")
      (node (ref "ATMEGA2560") (pin "15") (pinfunction "(OC4A)_PH3_15") (pintype "bidirectional"))
      (node (ref "R15") (pin "2") (pinfunction "2_2") (pintype "passive"))
    )
    (net (code "45") (name "/R-PWM") (class "Default")
      (node (ref "ATMEGA2560") (pin "25") (pinfunction "(OC1B/PCINT6)_PB6_25") (pintype "bidirectional"))
      (node (ref "R21") (pin "2") (pinfunction "2_2") (pintype "passive"))
    )
    (net (code "46") (name "/RELAY") (class "Default")
      (node (ref "ATMEGA2560") (pin "23") (pinfunction "(OC2A/PCINT4)_PB4_23") (pintype "bidirectional"))
      (node (ref "R19") (pin "2") (pinfunction "2_2") (pintype "passive"))
    )
    (net (code "47") (name "/RELAYINA") (class "Default")
      (node (ref "IC3") (pin "7") (pinfunction "OUT_7") (pintype "output"))
      (node (ref "Q9") (pin "1") (pinfunction "B_1") (pintype "passive"))
      (node (ref "R19") (pin "1") (pinfunction "1_1") (pintype "passive"))
      (node (ref "R43") (pin "2") (pinfunction "2_2") (pintype "passive"))
      (node (ref "R44") (pin "2") (pinfunction "2_2") (pintype "passive"))
      (node (ref "SJ1") (pin "1") (pinfunction "1_1") (pintype "passive"))
      (node (ref "SJ1") (pin "2") (pinfunction "2_2") (pintype "passive"))
    )
    (net (code "48") (name "/RX") (class "Default")
      (node (ref "IC2") (pin "1") (pinfunction "TXD_1") (pintype "output"))
      (node (ref "R35") (pin "2") (pinfunction "2_2") (pintype "passive"))
    )
    (net (code "49") (name "/RX1") (class "Default")
      (node (ref "ATMEGA2560") (pin "45") (pinfunction "(RXD1/INT2)_PD2_45") (pintype "bidirectional"))
      (node (ref "UART1") (pin "3") (pinfunction "3_3") (pintype "passive"))
    )
    (net (code "50") (name "/SCL") (class "Default")
      (node (ref "ATMEGA2560") (pin "43") (pinfunction "(SCL/INT0)_PD0_43") (pintype "bidirectional"))
      (node (ref "I2C") (pin "3") (pinfunction "3_3") (pintype "passive"))
      (node (ref "R4") (pin "2") (pinfunction "2_2") (pintype "passive"))
    )
    (net (code "51") (name "/SCLK") (class "Default")
      (node (ref "ATMEGA2560") (pin "20") (pinfunction "(SCK/PCINT1)_PB1_20") (pintype "bidirectional"))
      (node (ref "ICSP") (pin "3") (pinfunction "3_3") (pintype "passive"))
      (node (ref "SD") (pin "3") (pinfunction "3_3") (pintype "passive"))
      (node (ref "TP19") (pin "TP") (pinfunction "TP_TP") (pintype "input"))
    )
    (net (code "52") (name "/SDA") (class "Default")
      (node (ref "ATMEGA2560") (pin "44") (pinfunction "(SDA/INT1)_PD1_44") (pintype "bidirectional"))
      (node (ref "I2C") (pin "4") (pinfunction "4_4") (pintype "passive"))
      (node (ref "R5") (pin "2") (pinfunction "2_2") (pintype "passive"))
    )
    (net (code "53") (name "/SDSS") (class "Default")
      (node (ref "ATMEGA2560") (pin "19") (pinfunction "(~{SS/PCINT0})_PB0_19") (pintype "bidirectional"))
      (node (ref "SD") (pin "5") (pinfunction "5_5") (pintype "passive"))
      (node (ref "TP16") (pin "TP") (pinfunction "TP_TP") (pintype "input"))
    )
    (net (code "54") (name "/SUPPLY") (class "Default")
      (node (ref "C12") (pin "+") (pinfunction "+_+") (pintype "passive"))
      (node (ref "C13") (pin "+") (pinfunction "+_+") (pintype "passive"))
      (node (ref "C14") (pin "1") (pinfunction "1_1") (pintype "passive"))
      (node (ref "C16") (pin "1") (pinfunction "1_1") (pintype "passive"))
      (node (ref "K1") (pin "S") (pinfunction "S_S") (pintype "passive"))
      (node (ref "LEDS1") (pin "1") (pinfunction "1_1") (pintype "passive"))
      (node (ref "PWR24") (pin "A") (pinfunction "A_A") (pintype "passive"))
      (node (ref "RGBLEDS") (pin "1") (pinfunction "1_1") (pintype "passive"))
      (node (ref "SUPPLY") (pin "1") (pinfunction "1_1") (pintype "bidirectional"))
      (node (ref "SUPPLY") (pin "3") (pinfunction "3_3") (pintype "bidirectional"))
      (node (ref "TP2") (pin "TP") (pinfunction "TP_TP") (pintype "input"))
      (node (ref "VCC2") (pin "1") (pinfunction "1_1") (pintype "passive"))
    )
    (net (code "55") (name "/TX") (class "Default")
      (node (ref "IC2") (pin "5") (pinfunction "RXD_5") (pintype "input"))
      (node (ref "R36") (pin "2") (pinfunction "2_2") (pintype "passive"))
    )
    (net (code "56") (name "/TX1") (class "Default")
      (node (ref "ATMEGA2560") (pin "46") (pinfunction "(TXD1/INT3)_PD3_46") (pintype "bidirectional"))
      (node (ref "UART1") (pin "4") (pinfunction "4_4") (pintype "passive"))
    )
    (net (code "57") (name "/UART_N") (class "Default")
      (node (ref "ATMEGA2560") (pin "3") (pinfunction "(TXD0)_PE1_3") (pintype "bidirectional"))
      (node (ref "R36") (pin "1") (pinfunction "1_1") (pintype "passive"))
    )
    (net (code "58") (name "/UART_P") (class "Default")
      (node (ref "ATMEGA2560") (pin "2") (pinfunction "(RXD0/PCINT8)_PE0_2") (pintype "bidirectional"))
      (node (ref "R35") (pin "1") (pinfunction "1_1") (pintype "passive"))
    )
    (net (code "59") (name "/USBD+_P") (class "Default")
      (node (ref "IC2") (pin "15") (pinfunction "USBDP_15") (pintype "bidirectional"))
      (node (ref "R23") (pin "1") (pinfunction "1_1") (pintype "passive"))
      (node (ref "U$6") (pin "D+") (pinfunction "D+_D+") (pintype "bidirectional"))
    )
    (net (code "60") (name "/USBD-_N") (class "Default")
      (node (ref "IC2") (pin "16") (pinfunction "USBDM_16") (pintype "bidirectional"))
      (node (ref "R24") (pin "1") (pinfunction "1_1") (pintype "passive"))
      (node (ref "U$6") (pin "D-") (pinfunction "D-_D-") (pintype "bidirectional"))
    )
    (net (code "61") (name "/VCC2") (class "Default")
      (node (ref "+5V") (pin "1") (pinfunction "1_1") (pintype "passive"))
      (node (ref "+5V") (pin "3") (pinfunction "3_3") (pintype "passive"))
      (node (ref "D2") (pin "A") (pinfunction "A_A") (pintype "passive"))
      (node (ref "VCC2") (pin "2") (pinfunction "2_2") (pintype "passive"))
    )
    (net (code "62") (name "/X0-DIR") (class "Default")
      (node (ref "ATMEGA2560") (pin "68") (pinfunction "PJ5_(PCINT14)_68") (pintype "bidirectional"))
      (node (ref "L14") (pin "2") (pinfunction "2_2") (pintype "passive"))
      (node (ref "TP23") (pin "TP") (pinfunction "TP_TP") (pintype "input"))
    )
    (net (code "63") (name "/X0-STEP") (class "Default")
      (node (ref "ATMEGA2560") (pin "66") (pinfunction "PJ3_(PCINT12)_66") (pintype "bidirectional"))
      (node (ref "L12") (pin "2") (pinfunction "2_2") (pintype "passive"))
      (node (ref "TP21") (pin "TP") (pinfunction "TP_TP") (pintype "input"))
    )
    (net (code "64") (name "/X0-STOP") (class "Default")
      (node (ref "ATMEGA2560") (pin "69") (pinfunction "PJ6_(PCINT15)_69") (pintype "bidirectional"))
      (node (ref "X0") (pin "11") (pinfunction "11_11") (pintype "bidirectional"))
    )
    (net (code "65") (name "/X0-~{EN}") (class "Default")
      (node (ref "ATMEGA2560") (pin "67") (pinfunction "PJ4_(PCINT13)_67") (pintype "bidirectional"))
      (node (ref "L13") (pin "2") (pinfunction "2_2") (pintype "passive"))
      (node (ref "TP22") (pin "TP") (pinfunction "TP_TP") (pintype "input"))
    )
    (net (code "66") (name "/X1-DIR") (class "Default")
      (node (ref "ATMEGA2560") (pin "7") (pinfunction "(OC3C/INT5)_PE5_7") (pintype "bidirectional"))
      (node (ref "L17") (pin "2") (pinfunction "2_2") (pintype "passive"))
      (node (ref "TP26") (pin "TP") (pinfunction "TP_TP") (pintype "input"))
    )
    (net (code "67") (name "/X1-STEP") (class "Default")
      (node (ref "ATMEGA2560") (pin "5") (pinfunction "(OC3A/AIN1)_PE3_5") (pintype "bidirectional"))
      (node (ref "L15") (pin "2") (pinfunction "2_2") (pintype "passive"))
      (node (ref "TP24") (pin "TP") (pinfunction "TP_TP") (pintype "input"))
    )
    (net (code "68") (name "/X1-STOP") (class "Default")
      (node (ref "ATMEGA2560") (pin "8") (pinfunction "(T3/INT6)_PE6_8") (pintype "bidirectional"))
      (node (ref "X1") (pin "11") (pinfunction "11_11") (pintype "bidirectional"))
    )
    (net (code "69") (name "/X1-~{EN}") (class "Default")
      (node (ref "ATMEGA2560") (pin "6") (pinfunction "(OC3B/INT4)_PE4_6") (pintype "bidirectional"))
      (node (ref "L16") (pin "2") (pinfunction "2_2") (pintype "passive"))
      (node (ref "TP25") (pin "TP") (pinfunction "TP_TP") (pintype "input"))
    )
    (net (code "70") (name "/XTAL_N") (class "Default")
      (node (ref "ATMEGA2560") (pin "33") (pinfunction "XTAL2_33") (pintype "output"))
      (node (ref "C1") (pin "1") (pinfunction "1_1") (pintype "passive"))
      (node (ref "Y1") (pin "2") (pinfunction "2_2") (pintype "passive"))
    )
    (net (code "71") (name "/XTAL_P") (class "Default")
      (node (ref "ATMEGA2560") (pin "34") (pinfunction "XTAL1_34") (pintype "input"))
      (node (ref "C2") (pin "1") (pinfunction "1_1") (pintype "passive"))
      (node (ref "Y1") (pin "1") (pinfunction "1_1") (pintype "passive"))
    )
    (net (code "72") (name "/Y-DIR") (class "Default")
      (node (ref "ATMEGA2560") (pin "58") (pinfunction "PC5_(A13)_58") (pintype "bidirectional"))
      (node (ref "L20") (pin "2") (pinfunction "2_2") (pintype "passive"))
      (node (ref "TP29") (pin "TP") (pinfunction "TP_TP") (pintype "input"))
    )
    (net (code "73") (name "/Y-STEP") (class "Default")
      (node (ref "ATMEGA2560") (pin "60") (pinfunction "PC7_(A15)_60") (pintype "bidirectional"))
      (node (ref "L18") (pin "2") (pinfunction "2_2") (pintype "passive"))
      (node (ref "TP27") (pin "TP") (pinfunction "TP_TP") (pintype "input"))
    )
    (net (code "74") (name "/Y-STOP") (class "Default")
      (node (ref "ATMEGA2560") (pin "57") (pinfunction "PC4_(A12)_57") (pintype "bidirectional"))
      (node (ref "Y0") (pin "11") (pinfunction "11_11") (pintype "bidirectional"))
    )
    (net (code "75") (name "/Y-~{EN}") (class "Default")
      (node (ref "ATMEGA2560") (pin "59") (pinfunction "PC6_(A14)_59") (pintype "bidirectional"))
      (node (ref "L19") (pin "2") (pinfunction "2_2") (pintype "passive"))
      (node (ref "TP28") (pin "TP") (pinfunction "TP_TP") (pintype "input"))
    )
    (net (code "76") (name "/Z-DIR") (class "Default")
      (node (ref "ATMEGA2560") (pin "77") (pinfunction "PA1_(AD1)_77") (pintype "bidirectional"))
      (node (ref "L5") (pin "2") (pinfunction "2_2") (pintype "passive"))
      (node (ref "TP36") (pin "TP") (pinfunction "TP_TP") (pintype "input"))
    )
    (net (code "77") (name "/Z-STEP") (class "Default")
      (node (ref "ATMEGA2560") (pin "75") (pinfunction "PA3_(AD3)_75") (pintype "bidirectional"))
      (node (ref "L3") (pin "2") (pinfunction "2_2") (pintype "passive"))
      (node (ref "TP38") (pin "TP") (pinfunction "TP_TP") (pintype "input"))
    )
    (net (code "78") (name "/Z-STOP") (class "Default")
      (node (ref "Z") (pin "11") (pinfunction "11_11") (pintype "bidirectional"))
    )
    (net (code "79") (name "/Z-~{EN}") (class "Default")
      (node (ref "ATMEGA2560") (pin "76") (pinfunction "PA2_(AD2)_76") (pintype "bidirectional"))
      (node (ref "L4") (pin "2") (pinfunction "2_2") (pintype "passive"))
      (node (ref "TP37") (pin "TP") (pinfunction "TP_TP") (pintype "input"))
    )
    (net (code "80") (name "/Z0-ENDSTOP") (class "Default")
      (node (ref "HOTEND0") (pin "20") (pinfunction "20_20") (pintype "passive"))
      (node (ref "R26") (pin "1") (pinfunction "1_1") (pintype "passive"))
      (node (ref "R27") (pin "1") (pinfunction "1_1") (pintype "passive"))
    )
    (net (code "81") (name "/Z0-STOP") (class "Default")
      (node (ref "ATMEGA2560") (pin "56") (pinfunction "PC3_(A11)_56") (pintype "bidirectional"))
      (node (ref "C22") (pin "1") (pinfunction "1_1") (pintype "passive"))
      (node (ref "R27") (pin "2") (pinfunction "2_2") (pintype "passive"))
    )
    (net (code "82") (name "/Z1-ENDSTOP") (class "Default")
      (node (ref "HOTEND1") (pin "20") (pinfunction "20_20") (pintype "passive"))
      (node (ref "R29") (pin "1") (pinfunction "1_1") (pintype "passive"))
      (node (ref "R30") (pin "1") (pinfunction "1_1") (pintype "passive"))
    )
    (net (code "83") (name "/Z1-STOP") (class "Default")
      (node (ref "ATMEGA2560") (pin "41") (pinfunction "PL6_41") (pintype "bidirectional"))
      (node (ref "C23") (pin "1") (pinfunction "1_1") (pintype "passive"))
      (node (ref "R30") (pin "2") (pinfunction "2_2") (pintype "passive"))
    )
    (net (code "84") (name "/~{RESET}") (class "Default")
      (node (ref "ATMEGA2560") (pin "30") (pinfunction "~{RESET}_30") (pintype "input"))
      (node (ref "C19") (pin "2") (pinfunction "2_2") (pintype "passive"))
      (node (ref "C25") (pin "1") (pinfunction "1_1") (pintype "passive"))
      (node (ref "D10") (pin "A") (pinfunction "A_A") (pintype "passive"))
      (node (ref "ICSP") (pin "5") (pinfunction "5_5") (pintype "passive"))
      (node (ref "R32") (pin "1") (pinfunction "1_1") (pintype "passive"))
      (node (ref "R37") (pin "1") (pinfunction "1_1") (pintype "passive"))
    )
    (net (code "85") (name "GND") (class "Default")
      (node (ref "+24V") (pin "2") (pinfunction "2_2") (pintype "passive"))
      (node (ref "+24V") (pin "4") (pinfunction "4_4") (pintype "passive"))
      (node (ref "+5V") (pin "2") (pinfunction "2_2") (pintype "passive"))
      (node (ref "+5V") (pin "4") (pinfunction "4_4") (pintype "passive"))
      (node (ref "ATMEGA2560") (pin "11") (pinfunction "GND_2_11") (pintype "passive"))
      (node (ref "ATMEGA2560") (pin "32") (pinfunction "GND_4_32") (pintype "passive"))
      (node (ref "ATMEGA2560") (pin "62") (pinfunction "GND_3_62") (pintype "passive"))
      (node (ref "ATMEGA2560") (pin "81") (pinfunction "GND_5_81") (pintype "passive"))
      (node (ref "ATMEGA2560") (pin "99") (pinfunction "GND_99") (pintype "passive"))
      (node (ref "C10") (pin "2") (pinfunction "2_2") (pintype "passive"))
      (node (ref "C11") (pin "2") (pinfunction "2_2") (pintype "passive"))
      (node (ref "C12") (pin "-") (pinfunction "-_-") (pintype "passive"))
      (node (ref "C13") (pin "-") (pinfunction "-_-") (pintype "passive"))
      (node (ref "C14") (pin "2") (pinfunction "2_2") (pintype "passive"))
      (node (ref "C15") (pin "2") (pinfunction "2_2") (pintype "passive"))
      (node (ref "C16") (pin "2") (pinfunction "2_2") (pintype "passive"))
      (node (ref "C17") (pin "2") (pinfunction "2_2") (pintype "passive"))
      (node (ref "C18") (pin "2") (pinfunction "2_2") (pintype "passive"))
      (node (ref "C20") (pin "2") (pinfunction "2_2") (pintype "passive"))
      (node (ref "C21") (pin "2") (pinfunction "2_2") (pintype "passive"))
      (node (ref "C22") (pin "2") (pinfunction "2_2") (pintype "passive"))
      (node (ref "C23") (pin "2") (pinfunction "2_2") (pintype "passive"))
      (node (ref "C24") (pin "2") (pinfunction "2_2") (pintype "passive"))
      (node (ref "C25") (pin "2") (pinfunction "2_2") (pintype "passive"))
      (node (ref "C3") (pin "2") (pinfunction "2_2") (pintype "passive"))
      (node (ref "C4") (pin "2") (pinfunction "2_2") (pintype "passive"))
      (node (ref "C5") (pin "2") (pinfunction "2_2") (pintype "passive"))
      (node (ref "C6") (pin "2") (pinfunction "2_2") (pintype "passive"))
      (node (ref "C7") (pin "2") (pinfunction "2_2") (pintype "passive"))
      (node (ref "C8") (pin "-") (pinfunction "-_-") (pintype "passive"))
      (node (ref "C9") (pin "2") (pinfunction "2_2") (pintype "passive"))
      (node (ref "D1") (pin "A") (pinfunction "A_A") (pintype "passive"))
      (node (ref "E0") (pin "10") (pinfunction "10_10") (pintype "bidirectional"))
      (node (ref "E0") (pin "13") (pinfunction "13_13") (pintype "bidirectional"))
      (node (ref "E0") (pin "15") (pinfunction "15_15") (pintype "bidirectional"))
      (node (ref "E0") (pin "2") (pinfunction "2_2") (pintype "bidirectional"))
      (node (ref "E0") (pin "4") (pinfunction "4_4") (pintype "bidirectional"))
      (node (ref "E0") (pin "8") (pinfunction "8_8") (pintype "bidirectional"))
      (node (ref "E0") (pin "GND@1") (pinfunction "GND_GND@1") (pintype "bidirectional"))
      (node (ref "E0") (pin "GND@2") (pinfunction "GND_GND@2") (pintype "bidirectional"))
      (node (ref "E1") (pin "10") (pinfunction "10_10") (pintype "bidirectional"))
      (node (ref "E1") (pin "13") (pinfunction "13_13") (pintype "bidirectional"))
      (node (ref "E1") (pin "15") (pinfunction "15_15") (pintype "bidirectional"))
      (node (ref "E1") (pin "2") (pinfunction "2_2") (pintype "bidirectional"))
      (node (ref "E1") (pin "4") (pinfunction "4_4") (pintype "bidirectional"))
      (node (ref "E1") (pin "8") (pinfunction "8_8") (pintype "bidirectional"))
      (node (ref "E1") (pin "GND@1") (pinfunction "GND_GND@1") (pintype "bidirectional"))
      (node (ref "E1") (pin "GND@2") (pinfunction "GND_GND@2") (pintype "bidirectional"))
      (node (ref "HEATEDBED") (pin "2") (pinfunction "2_2") (pintype "bidirectional"))
      (node (ref "HOTEND0") (pin "11") (pinfunction "11_11") (pintype "passive"))
      (node (ref "HOTEND0") (pin "17") (pinfunction "17_17") (pintype "passive"))
      (node (ref "HOTEND0") (pin "2") (pinfunction "2_2") (pintype "passive"))
      (node (ref "HOTEND0") (pin "4") (pinfunction "4_4") (pintype "passive"))
      (node (ref "HOTEND0") (pin "7") (pinfunction "7_7") (pintype "passive"))
      (node (ref "HOTEND0") (pin "9") (pinfunction "9_9") (pintype "passive"))
      (node (ref "HOTEND1") (pin "11") (pinfunction "11_11") (pintype "passive"))
      (node (ref "HOTEND1") (pin "17") (pinfunction "17_17") (pintype "passive"))
      (node (ref "HOTEND1") (pin "2") (pinfunction "2_2") (pintype "passive"))
      (node (ref "HOTEND1") (pin "4") (pinfunction "4_4") (pintype "passive"))
      (node (ref "HOTEND1") (pin "7") (pinfunction "7_7") (pintype "passive"))
      (node (ref "HOTEND1") (pin "9") (pinfunction "9_9") (pintype "passive"))
      (node (ref "I2C") (pin "2") (pinfunction "2_2") (pintype "passive"))
      (node (ref "IC1") (pin "4") (pinfunction "V-_4") (pintype "power_in"))
      (node (ref "IC2") (pin "18") (pinfunction "GND_18") (pintype "power_in"))
      (node (ref "IC2") (pin "21") (pinfunction "GND_21") (pintype "power_in"))
      (node (ref "IC2") (pin "25") (pinfunction "GND_25") (pintype "power_in"))
      (node (ref "IC2") (pin "26") (pinfunction "TEST_26") (pintype "input"))
      (node (ref "IC2") (pin "7") (pinfunction "GND_7") (pintype "power_in"))
      (node (ref "IC3") (pin "1") (pinfunction "GND_1") (pintype "passive"))
      (node (ref "IC3") (pin "4") (pinfunction "V-_4") (pintype "power_in"))
      (node (ref "ICSP") (pin "6") (pinfunction "6_6") (pintype "passive"))
      (node (ref "L21") (pin "1") (pinfunction "1_1") (pintype "passive"))
      (node (ref "LCD") (pin "4") (pinfunction "4_4") (pintype "passive"))
      (node (ref "LCD") (pin "6") (pinfunction "6_6") (pintype "passive"))
      (node (ref "LM2595") (pin "3") (pinfunction "GND_3") (pintype "power_in"))
      (node (ref "LM2595") (pin "5") (pinfunction "EN_5") (pintype "input"))
      (node (ref "LM2595") (pin "6") (pinfunction "GND_6") (pintype "power_in"))
      (node (ref "Q1") (pin "1") (pinfunction "S_1") (pintype "passive"))
      (node (ref "Q1") (pin "2") (pinfunction "S_2") (pintype "passive"))
      (node (ref "Q1") (pin "3") (pinfunction "S_3") (pintype "passive"))
      (node (ref "Q2") (pin "1") (pinfunction "S_1") (pintype "passive"))
      (node (ref "Q2") (pin "2") (pinfunction "S_2") (pintype "passive"))
      (node (ref "Q2") (pin "3") (pinfunction "S_3") (pintype "passive"))
      (node (ref "Q3") (pin "1") (pinfunction "S_1") (pintype "passive"))
      (node (ref "Q3") (pin "2") (pinfunction "S_2") (pintype "passive"))
      (node (ref "Q3") (pin "3") (pinfunction "S_3") (pintype "passive"))
      (node (ref "Q4") (pin "2") (pinfunction "E_2") (pintype "passive"))
      (node (ref "Q5") (pin "2") (pinfunction "E_2") (pintype "passive"))
      (node (ref "Q6") (pin "2") (pinfunction "S_2") (pintype "bidirectional"))
      (node (ref "Q7") (pin "2") (pinfunction "S_2") (pintype "bidirectional"))
      (node (ref "Q8") (pin "2") (pinfunction "S_2") (pintype "bidirectional"))
      (node (ref "Q9") (pin "2") (pinfunction "E_2") (pintype "passive"))
      (node (ref "R10") (pin "2") (pinfunction "2_2") (pintype "passive"))
      (node (ref "R13") (pin "2") (pinfunction "2_2") (pintype "passive"))
      (node (ref "R18") (pin "2") (pinfunction "2_2") (pintype "passive"))
      (node (ref "R23") (pin "2") (pinfunction "2_2") (pintype "passive"))
      (node (ref "R24") (pin "2") (pinfunction "2_2") (pintype "passive"))
      (node (ref "R25") (pin "2") (pinfunction "2_2") (pintype "passive"))
      (node (ref "R31") (pin "2") (pinfunction "2_2") (pintype "passive"))
      (node (ref "R38") (pin "1") (pinfunction "1_1") (pintype "passive"))
      (node (ref "R39") (pin "1") (pinfunction "1_1") (pintype "passive"))
      (node (ref "R40") (pin "2") (pinfunction "2_2") (pintype "passive"))
      (node (ref "R41") (pin "1") (pinfunction "1_1") (pintype "passive"))
      (node (ref "R42") (pin "2") (pinfunction "2_2") (pintype "passive"))
      (node (ref "R7") (pin "2") (pinfunction "2_2") (pintype "passive"))
      (node (ref "RESET") (pin "A") (pinfunction "P_A") (pintype "passive"))
      (node (ref "RESET") (pin "A'") (pinfunction "P1_A'") (pintype "passive"))
      (node (ref "SD") (pin "1") (pinfunction "1_1") (pintype "passive"))
      (node (ref "SH1") (pin "1") (pinfunction "P$1_1") (pintype "bidirectional"))
      (node (ref "STAT") (pin "C") (pinfunction "C_C") (pintype "passive"))
      (node (ref "SUPPLY") (pin "2") (pinfunction "2_2") (pintype "bidirectional"))
      (node (ref "SUPPLY") (pin "4") (pinfunction "4_4") (pintype "bidirectional"))
      (node (ref "TP1") (pin "TP") (pinfunction "TP_TP") (pintype "input"))
      (node (ref "U$6") (pin "GND") (pinfunction "GND_GND") (pintype "bidirectional"))
      (node (ref "U1") (pin "2") (pinfunction "GND_2") (pintype "bidirectional"))
      (node (ref "UART1") (pin "2") (pinfunction "2_2") (pintype "passive"))
      (node (ref "X0") (pin "10") (pinfunction "10_10") (pintype "bidirectional"))
      (node (ref "X0") (pin "13") (pinfunction "13_13") (pintype "bidirectional"))
      (node (ref "X0") (pin "15") (pinfunction "15_15") (pintype "bidirectional"))
      (node (ref "X0") (pin "2") (pinfunction "2_2") (pintype "bidirectional"))
      (node (ref "X0") (pin "4") (pinfunction "4_4") (pintype "bidirectional"))
      (node (ref "X0") (pin "8") (pinfunction "8_8") (pintype "bidirectional"))
      (node (ref "X0") (pin "GND@1") (pinfunction "GND_GND@1") (pintype "bidirectional"))
      (node (ref "X0") (pin "GND@2") (pinfunction "GND_GND@2") (pintype "bidirectional"))
      (node (ref "X1") (pin "10") (pinfunction "10_10") (pintype "bidirectional"))
      (node (ref "X1") (pin "13") (pinfunction "13_13") (pintype "bidirectional"))
      (node (ref "X1") (pin "15") (pinfunction "15_15") (pintype "bidirectional"))
      (node (ref "X1") (pin "2") (pinfunction "2_2") (pintype "bidirectional"))
      (node (ref "X1") (pin "4") (pinfunction "4_4") (pintype "bidirectional"))
      (node (ref "X1") (pin "8") (pinfunction "8_8") (pintype "bidirectional"))
      (node (ref "X1") (pin "GND@1") (pinfunction "GND_GND@1") (pintype "bidirectional"))
      (node (ref "X1") (pin "GND@2") (pinfunction "GND_GND@2") (pintype "bidirectional"))
      (node (ref "Y0") (pin "10") (pinfunction "10_10") (pintype "bidirectional"))
      (node (ref "Y0") (pin "13") (pinfunction "13_13") (pintype "bidirectional"))
      (node (ref "Y0") (pin "15") (pinfunction "15_15") (pintype "bidirectional"))
      (node (ref "Y0") (pin "2") (pinfunction "2_2") (pintype "bidirectional"))
      (node (ref "Y0") (pin "4") (pinfunction "4_4") (pintype "bidirectional"))
      (node (ref "Y0") (pin "8") (pinfunction "8_8") (pintype "bidirectional"))
      (node (ref "Y0") (pin "GND@1") (pinfunction "GND_GND@1") (pintype "bidirectional"))
      (node (ref "Z") (pin "10") (pinfunction "10_10") (pintype "bidirectional"))
      (node (ref "Z") (pin "13") (pinfunction "13_13") (pintype "bidirectional"))
      (node (ref "Z") (pin "15") (pinfunction "15_15") (pintype "bidirectional"))
      (node (ref "Z") (pin "2") (pinfunction "2_2") (pintype "bidirectional"))
      (node (ref "Z") (pin "4") (pinfunction "4_4") (pintype "bidirectional"))
      (node (ref "Z") (pin "8") (pinfunction "8_8") (pintype "bidirectional"))
      (node (ref "Z") (pin "GND@1") (pinfunction "GND_GND@1") (pintype "bidirectional"))
      (node (ref "Z") (pin "GND@2") (pinfunction "GND_GND@2") (pintype "bidirectional"))
    )
    (net (code "86") (name "Net-(ATMEGA2560-AREF)") (class "Default")
      (node (ref "ATMEGA2560") (pin "98") (pinfunction "AREF_98") (pintype "input"))
      (node (ref "C6") (pin "1") (pinfunction "1_1") (pintype "passive"))
    )
    (net (code "87") (name "Net-(D8-PadA)") (class "Default")
      (node (ref "D8") (pin "A") (pinfunction "A_A") (pintype "passive"))
      (node (ref "L2") (pin "2") (pinfunction "2_2") (pintype "passive"))
    )
    (net (code "88") (name "Net-(E0-Pad6)") (class "Default")
      (node (ref "E0") (pin "6") (pinfunction "6_6") (pintype "bidirectional"))
      (node (ref "L6") (pin "2") (pinfunction "2_2") (pintype "passive"))
    )
    (net (code "89") (name "Net-(E0-Pad7)") (class "Default")
      (node (ref "E0") (pin "7") (pinfunction "7_7") (pintype "bidirectional"))
      (node (ref "L7") (pin "2") (pinfunction "2_2") (pintype "passive"))
    )
    (net (code "90") (name "Net-(E0-Pad9)") (class "Default")
      (node (ref "E0") (pin "9") (pinfunction "9_9") (pintype "bidirectional"))
      (node (ref "L8") (pin "2") (pinfunction "2_2") (pintype "passive"))
    )
    (net (code "91") (name "Net-(E1-Pad6)") (class "Default")
      (node (ref "E1") (pin "6") (pinfunction "6_6") (pintype "bidirectional"))
      (node (ref "L9") (pin "1") (pinfunction "1_1") (pintype "passive"))
    )
    (net (code "92") (name "Net-(E1-Pad7)") (class "Default")
      (node (ref "E1") (pin "7") (pinfunction "7_7") (pintype "bidirectional"))
      (node (ref "L10") (pin "1") (pinfunction "1_1") (pintype "passive"))
    )
    (net (code "93") (name "Net-(E1-Pad9)") (class "Default")
      (node (ref "E1") (pin "9") (pinfunction "9_9") (pintype "bidirectional"))
      (node (ref "L11") (pin "1") (pinfunction "1_1") (pintype "passive"))
    )
    (net (code "94") (name "Net-(F3-Pad1)") (class "Default")
      (node (ref "F3") (pin "1") (pinfunction "1_1") (pintype "passive"))
      (node (ref "R25") (pin "1") (pinfunction "1_1") (pintype "passive"))
      (node (ref "U$6") (pin "VBUS") (pinfunction "VBUS_VBUS") (pintype "bidirectional"))
    )
    (net (code "95") (name "Net-(F3-Pad2)") (class "Default")
      (node (ref "F3") (pin "2") (pinfunction "2_2") (pintype "passive"))
      (node (ref "L2") (pin "1") (pinfunction "1_1") (pintype "passive"))
    )
    (net (code "96") (name "Net-(IC1A--IN)") (class "Default")
      (node (ref "IC1") (pin "1") (pinfunction "OUT_1") (pintype "output"))
      (node (ref "IC1") (pin "2") (pinfunction "-IN_2") (pintype "input"))
      (node (ref "R3") (pin "2") (pinfunction "2_2") (pintype "passive"))
    )
    (net (code "97") (name "Net-(IC2-3V3OUT)") (class "Default")
      (node (ref "C20") (pin "1") (pinfunction "1_1") (pintype "passive"))
      (node (ref "IC2") (pin "17") (pinfunction "3V3OUT_17") (pintype "output"))
    )
    (net (code "98") (name "Net-(IC2-CBUS0)") (class "Default")
      (node (ref "IC2") (pin "23") (pinfunction "CBUS0_23") (pintype "bidirectional"))
      (node (ref "TXLED") (pin "C") (pinfunction "C_C") (pintype "passive"))
    )
    (net (code "99") (name "Net-(IC2-CBUS1)") (class "Default")
      (node (ref "IC2") (pin "22") (pinfunction "CBUS1_22") (pintype "bidirectional"))
      (node (ref "RXLED") (pin "C") (pinfunction "C_C") (pintype "passive"))
    )
    (net (code "100") (name "Net-(IC2-~{DTR})") (class "Default")
      (node (ref "C19") (pin "1") (pinfunction "1_1") (pintype "passive"))
      (node (ref "IC2") (pin "2") (pinfunction "~{DTR}_2") (pintype "output"))
    )
    (net (code "101") (name "Net-(IC3-+IN)") (class "Default")
      (node (ref "IC3") (pin "2") (pinfunction "+IN_2") (pintype "input"))
      (node (ref "R1") (pin "2") (pinfunction "2_2") (pintype "passive"))
      (node (ref "R42") (pin "1") (pinfunction "1_1") (pintype "passive"))
      (node (ref "R44") (pin "1") (pinfunction "1_1") (pintype "passive"))
    )
    (net (code "102") (name "Net-(L1-1)") (class "Default")
      (node (ref "D1") (pin "C") (pinfunction "C_C") (pintype "passive"))
      (node (ref "L1") (pin "A") (pinfunction "1_A") (pintype "passive"))
      (node (ref "LM2595") (pin "1") (pinfunction "OUT_1") (pintype "output"))
    )
    (net (code "103") (name "Net-(L3-Pad1)") (class "Default")
      (node (ref "L3") (pin "1") (pinfunction "1_1") (pintype "passive"))
      (node (ref "Z") (pin "6") (pinfunction "6_6") (pintype "bidirectional"))
    )
    (net (code "104") (name "Net-(L4-Pad1)") (class "Default")
      (node (ref "L4") (pin "1") (pinfunction "1_1") (pintype "passive"))
      (node (ref "Z") (pin "7") (pinfunction "7_7") (pintype "bidirectional"))
    )
    (net (code "105") (name "Net-(L5-Pad1)") (class "Default")
      (node (ref "L5") (pin "1") (pinfunction "1_1") (pintype "passive"))
      (node (ref "Z") (pin "9") (pinfunction "9_9") (pintype "bidirectional"))
    )
    (net (code "106") (name "Net-(L12-Pad1)") (class "Default")
      (node (ref "L12") (pin "1") (pinfunction "1_1") (pintype "passive"))
      (node (ref "X0") (pin "6") (pinfunction "6_6") (pintype "bidirectional"))
    )
    (net (code "107") (name "Net-(L13-Pad1)") (class "Default")
      (node (ref "L13") (pin "1") (pinfunction "1_1") (pintype "passive"))
      (node (ref "X0") (pin "7") (pinfunction "7_7") (pintype "bidirectional"))
    )
    (net (code "108") (name "Net-(L14-Pad1)") (class "Default")
      (node (ref "L14") (pin "1") (pinfunction "1_1") (pintype "passive"))
      (node (ref "X0") (pin "9") (pinfunction "9_9") (pintype "bidirectional"))
    )
    (net (code "109") (name "Net-(L15-Pad1)") (class "Default")
      (node (ref "L15") (pin "1") (pinfunction "1_1") (pintype "passive"))
      (node (ref "X1") (pin "6") (pinfunction "6_6") (pintype "bidirectional"))
    )
    (net (code "110") (name "Net-(L16-Pad1)") (class "Default")
      (node (ref "L16") (pin "1") (pinfunction "1_1") (pintype "passive"))
      (node (ref "X1") (pin "7") (pinfunction "7_7") (pintype "bidirectional"))
    )
    (net (code "111") (name "Net-(L17-Pad1)") (class "Default")
      (node (ref "L17") (pin "1") (pinfunction "1_1") (pintype "passive"))
      (node (ref "X1") (pin "9") (pinfunction "9_9") (pintype "bidirectional"))
    )
    (net (code "112") (name "Net-(L18-Pad1)") (class "Default")
      (node (ref "L18") (pin "1") (pinfunction "1_1") (pintype "passive"))
      (node (ref "Y0") (pin "6") (pinfunction "6_6") (pintype "bidirectional"))
    )
    (net (code "113") (name "Net-(L19-Pad1)") (class "Default")
      (node (ref "L19") (pin "1") (pinfunction "1_1") (pintype "passive"))
      (node (ref "Y0") (pin "7") (pinfunction "7_7") (pintype "bidirectional"))
    )
    (net (code "114") (name "Net-(L20-Pad1)") (class "Default")
      (node (ref "L20") (pin "1") (pinfunction "1_1") (pintype "passive"))
      (node (ref "Y0") (pin "9") (pinfunction "9_9") (pintype "bidirectional"))
    )
    (net (code "115") (name "Net-(LED1-PadC)") (class "Default")
      (node (ref "LED1") (pin "C") (pinfunction "C_C") (pintype "passive"))
      (node (ref "R2") (pin "2") (pinfunction "2_2") (pintype "passive"))
    )
    (net (code "116") (name "Net-(LED2-PadC)") (class "Default")
      (node (ref "LED2") (pin "C") (pinfunction "C_C") (pintype "passive"))
      (node (ref "R8") (pin "2") (pinfunction "2_2") (pintype "passive"))
    )
    (net (code "117") (name "Net-(LED3-PadC)") (class "Default")
      (node (ref "LED3") (pin "C") (pinfunction "C_C") (pintype "passive"))
      (node (ref "R11") (pin "2") (pinfunction "2_2") (pintype "passive"))
    )
    (net (code "118") (name "Net-(PWR5-PadC)") (class "Default")
      (node (ref "PWR5") (pin "C") (pinfunction "C_C") (pintype "passive"))
      (node (ref "R39") (pin "2") (pinfunction "2_2") (pintype "passive"))
    )
    (net (code "119") (name "Net-(PWR24-PadC)") (class "Default")
      (node (ref "PWR24") (pin "C") (pinfunction "C_C") (pintype "passive"))
      (node (ref "R38") (pin "2") (pinfunction "2_2") (pintype "passive"))
    )
    (net (code "120") (name "Net-(Q1-G)") (class "Default")
      (node (ref "Q1") (pin "4") (pinfunction "G_4") (pintype "passive"))
      (node (ref "R6") (pin "1") (pinfunction "1_1") (pintype "passive"))
      (node (ref "R7") (pin "1") (pinfunction "1_1") (pintype "passive"))
    )
    (net (code "121") (name "Net-(Q2-G)") (class "Default")
      (node (ref "Q2") (pin "4") (pinfunction "G_4") (pintype "passive"))
      (node (ref "R10") (pin "1") (pinfunction "1_1") (pintype "passive"))
      (node (ref "R9") (pin "1") (pinfunction "1_1") (pintype "passive"))
    )
    (net (code "122") (name "Net-(Q3-G)") (class "Default")
      (node (ref "Q3") (pin "4") (pinfunction "G_4") (pintype "passive"))
      (node (ref "R12") (pin "1") (pinfunction "1_1") (pintype "passive"))
      (node (ref "R13") (pin "1") (pinfunction "1_1") (pintype "passive"))
    )
    (net (code "123") (name "Net-(Q4-B)") (class "Default")
      (node (ref "Q4") (pin "1") (pinfunction "B_1") (pintype "passive"))
      (node (ref "R14") (pin "1") (pinfunction "1_1") (pintype "passive"))
    )
    (net (code "124") (name "Net-(Q5-B)") (class "Default")
      (node (ref "Q5") (pin "1") (pinfunction "B_1") (pintype "passive"))
      (node (ref "R15") (pin "1") (pinfunction "1_1") (pintype "passive"))
    )
    (net (code "125") (name "Net-(Q6-D)") (class "Default")
      (node (ref "LEDS1") (pin "2") (pinfunction "2_2") (pintype "passive"))
      (node (ref "Q6") (pin "3") (pinfunction "D_3") (pintype "bidirectional"))
      (node (ref "RGBLEDS") (pin "2") (pinfunction "2_2") (pintype "passive"))
    )
    (net (code "126") (name "Net-(Q6-G)") (class "Default")
      (node (ref "Q6") (pin "1") (pinfunction "G_1") (pintype "bidirectional"))
      (node (ref "R18") (pin "1") (pinfunction "1_1") (pintype "passive"))
      (node (ref "R20") (pin "1") (pinfunction "1_1") (pintype "passive"))
    )
    (net (code "127") (name "Net-(Q7-D)") (class "Default")
      (node (ref "LEDS1") (pin "3") (pinfunction "3_3") (pintype "passive"))
      (node (ref "Q7") (pin "3") (pinfunction "D_3") (pintype "bidirectional"))
      (node (ref "RGBLEDS") (pin "3") (pinfunction "3_3") (pintype "passive"))
    )
    (net (code "128") (name "Net-(Q7-G)") (class "Default")
      (node (ref "Q7") (pin "1") (pinfunction "G_1") (pintype "bidirectional"))
      (node (ref "R21") (pin "1") (pinfunction "1_1") (pintype "passive"))
      (node (ref "R31") (pin "1") (pinfunction "1_1") (pintype "passive"))
    )
    (net (code "129") (name "Net-(Q8-D)") (class "Default")
      (node (ref "LEDS1") (pin "4") (pinfunction "4_4") (pintype "passive"))
      (node (ref "Q8") (pin "3") (pinfunction "D_3") (pintype "bidirectional"))
      (node (ref "RGBLEDS") (pin "4") (pinfunction "4_4") (pintype "passive"))
    )
    (net (code "130") (name "Net-(Q8-G)") (class "Default")
      (node (ref "Q8") (pin "1") (pinfunction "G_1") (pintype "bidirectional"))
      (node (ref "R22") (pin "1") (pinfunction "1_1") (pintype "passive"))
      (node (ref "R40") (pin "1") (pinfunction "1_1") (pintype "passive"))
    )
    (net (code "131") (name "Net-(Q9-C)") (class "Default")
      (node (ref "D4") (pin "A") (pinfunction "A_A") (pintype "passive"))
      (node (ref "K1") (pin "2") (pinfunction "2_2") (pintype "passive"))
      (node (ref "Q9") (pin "3") (pinfunction "C_3") (pintype "passive"))
    )
    (net (code "132") (name "Net-(R3-Pad1)") (class "Default")
      (node (ref "R3") (pin "1") (pinfunction "1_1") (pintype "passive"))
      (node (ref "STAT") (pin "A") (pinfunction "A_A") (pintype "passive"))
    )
    (net (code "133") (name "Net-(R33-Pad1)") (class "Default")
      (node (ref "R33") (pin "1") (pinfunction "1_1") (pintype "passive"))
      (node (ref "TXLED") (pin "A") (pinfunction "A_A") (pintype "passive"))
    )
    (net (code "134") (name "Net-(R34-Pad1)") (class "Default")
      (node (ref "R34") (pin "1") (pinfunction "1_1") (pintype "passive"))
      (node (ref "RXLED") (pin "A") (pinfunction "A_A") (pintype "passive"))
    )
    (net (code "135") (name "Net-(RESET-S)") (class "Default")
      (node (ref "R32") (pin "2") (pinfunction "2_2") (pintype "passive"))
      (node (ref "RESET") (pin "B") (pinfunction "S_B") (pintype "passive"))
      (node (ref "RESET") (pin "B'") (pinfunction "S1_B'") (pintype "passive"))
    )
    (net (code "136") (name "unconnected-(ATMEGA2560-(CLKO{slash}ICP3{slash}INT7)_PE7-Pad9)") (class "Default")
      (node (ref "ATMEGA2560") (pin "9") (pinfunction "(CLKO/ICP3/INT7)_PE7_9") (pintype "bidirectional"))
    )
    (net (code "137") (name "unconnected-(ATMEGA2560-(ICP1)_PD4-Pad47)") (class "Default")
      (node (ref "ATMEGA2560") (pin "47") (pinfunction "(ICP1)_PD4_47") (pintype "bidirectional"))
    )
    (net (code "138") (name "unconnected-(ATMEGA2560-(ICP4)_PL0-Pad35)") (class "Default")
      (node (ref "ATMEGA2560") (pin "35") (pinfunction "(ICP4)_PL0_35") (pintype "bidirectional"))
    )
    (net (code "139") (name "unconnected-(ATMEGA2560-(ICP5)_PL1-Pad36)") (class "Default")
      (node (ref "ATMEGA2560") (pin "36") (pinfunction "(ICP5)_PL1_36") (pintype "bidirectional"))
    )
    (net (code "140") (name "unconnected-(ATMEGA2560-(OC0B)_PG5-Pad1)") (class "Default")
      (node (ref "ATMEGA2560") (pin "1") (pinfunction "(OC0B)_PG5_1") (pintype "bidirectional"))
    )
    (net (code "141") (name "unconnected-(ATMEGA2560-(OC4C)_PH5-Pad17)") (class "Default")
      (node (ref "ATMEGA2560") (pin "17") (pinfunction "(OC4C)_PH5_17") (pintype "bidirectional"))
    )
    (net (code "142") (name "unconnected-(ATMEGA2560-(T0)_PD7-Pad50)") (class "Default")
      (node (ref "ATMEGA2560") (pin "50") (pinfunction "(T0)_PD7_50") (pintype "bidirectional"))
    )
    (net (code "143") (name "unconnected-(ATMEGA2560-(T1)_PD6-Pad49)") (class "Default")
      (node (ref "ATMEGA2560") (pin "49") (pinfunction "(T1)_PD6_49") (pintype "bidirectional"))
    )
    (net (code "144") (name "unconnected-(ATMEGA2560-(T4)_PH7-Pad27)") (class "Default")
      (node (ref "ATMEGA2560") (pin "27") (pinfunction "(T4)_PH7_27") (pintype "bidirectional"))
    )
    (net (code "145") (name "unconnected-(ATMEGA2560-(T5)_PL2-Pad37)") (class "Default")
      (node (ref "ATMEGA2560") (pin "37") (pinfunction "(T5)_PL2_37") (pintype "bidirectional"))
    )
    (net (code "146") (name "unconnected-(ATMEGA2560-(TOSC1)_PG4-Pad29)") (class "Default")
      (node (ref "ATMEGA2560") (pin "29") (pinfunction "(TOSC1)_PG4_29") (pintype "bidirectional"))
    )
    (net (code "147") (name "unconnected-(ATMEGA2560-(TOSC2)_PG3-Pad28)") (class "Default")
      (node (ref "ATMEGA2560") (pin "28") (pinfunction "(TOSC2)_PG3_28") (pintype "bidirectional"))
    )
    (net (code "148") (name "unconnected-(ATMEGA2560-(XCK0{slash}AIN0)_PE2-Pad4)") (class "Default")
      (node (ref "ATMEGA2560") (pin "4") (pinfunction "(XCK0/AIN0)_PE2_4") (pintype "bidirectional"))
    )
    (net (code "149") (name "unconnected-(ATMEGA2560-(XCK1)_PD5-Pad48)") (class "Default")
      (node (ref "ATMEGA2560") (pin "48") (pinfunction "(XCK1)_PD5_48") (pintype "bidirectional"))
    )
    (net (code "150") (name "unconnected-(ATMEGA2560-(XCK2)_PH2-Pad14)") (class "Default")
      (node (ref "ATMEGA2560") (pin "14") (pinfunction "(XCK2)_PH2_14") (pintype "bidirectional"))
    )
    (net (code "151") (name "unconnected-(ATMEGA2560-PA0_(AD0)-Pad78)") (class "Default")
      (node (ref "ATMEGA2560") (pin "78") (pinfunction "PA0_(AD0)_78") (pintype "bidirectional"))
    )
    (net (code "152") (name "unconnected-(ATMEGA2560-PC0_(A8)-Pad53)") (class "Default")
      (node (ref "ATMEGA2560") (pin "53") (pinfunction "PC0_(A8)_53") (pintype "bidirectional"))
    )
    (net (code "153") (name "unconnected-(ATMEGA2560-PC1_(A9)-Pad54)") (class "Default")
      (node (ref "ATMEGA2560") (pin "54") (pinfunction "PC1_(A9)_54") (pintype "bidirectional"))
    )
    (net (code "154") (name "unconnected-(ATMEGA2560-PC2_(A10)-Pad55)") (class "Default")
      (node (ref "ATMEGA2560") (pin "55") (pinfunction "PC2_(A10)_55") (pintype "bidirectional"))
    )
    (net (code "155") (name "unconnected-(ATMEGA2560-PF4_(ADC4{slash}TCK)-Pad93)") (class "Default")
      (node (ref "ATMEGA2560") (pin "93") (pinfunction "PF4_(ADC4/TCK)_93") (pintype "bidirectional"))
    )
    (net (code "156") (name "unconnected-(ATMEGA2560-PF5_(ADC5{slash}TMS)-Pad92)") (class "Default")
      (node (ref "ATMEGA2560") (pin "92") (pinfunction "PF5_(ADC5/TMS)_92") (pintype "bidirectional"))
    )
    (net (code "157") (name "unconnected-(ATMEGA2560-PF6_(ADC6{slash}TDO)-Pad91)") (class "Default")
      (node (ref "ATMEGA2560") (pin "91") (pinfunction "PF6_(ADC6/TDO)_91") (pintype "bidirectional"))
    )
    (net (code "158") (name "unconnected-(ATMEGA2560-PF7_(ADC7{slash}TDI)-Pad90)") (class "Default")
      (node (ref "ATMEGA2560") (pin "90") (pinfunction "PF7_(ADC7/TDI)_90") (pintype "bidirectional"))
    )
    (net (code "159") (name "unconnected-(ATMEGA2560-PG0_(~{WR})-Pad51)") (class "Default")
      (node (ref "ATMEGA2560") (pin "51") (pinfunction "PG0_(~{WR})_51") (pintype "bidirectional"))
    )
    (net (code "160") (name "unconnected-(ATMEGA2560-PG1_(~{RD})-Pad52)") (class "Default")
      (node (ref "ATMEGA2560") (pin "52") (pinfunction "PG1_(~{RD})_52") (pintype "bidirectional"))
    )
    (net (code "161") (name "unconnected-(ATMEGA2560-PG2_(ALE)-Pad70)") (class "Default")
      (node (ref "ATMEGA2560") (pin "70") (pinfunction "PG2_(ALE)_70") (pintype "bidirectional"))
    )
    (net (code "162") (name "unconnected-(ATMEGA2560-PJ0_(RXD3{slash}PCINT9)-Pad63)") (class "Default")
      (node (ref "ATMEGA2560") (pin "63") (pinfunction "PJ0_(RXD3/PCINT9)_63") (pintype "bidirectional"))
    )
    (net (code "163") (name "unconnected-(ATMEGA2560-PJ1_(TXD3{slash}PCINT10)-Pad64)") (class "Default")
      (node (ref "ATMEGA2560") (pin "64") (pinfunction "PJ1_(TXD3/PCINT10)_64") (pintype "bidirectional"))
    )
    (net (code "164") (name "unconnected-(ATMEGA2560-PJ2_(XCK3{slash}PCINT11)-Pad65)") (class "Default")
      (node (ref "ATMEGA2560") (pin "65") (pinfunction "PJ2_(XCK3/PCINT11)_65") (pintype "bidirectional"))
    )
    (net (code "165") (name "unconnected-(ATMEGA2560-PJ7-Pad79)") (class "Default")
      (node (ref "ATMEGA2560") (pin "79") (pinfunction "PJ7_79") (pintype "bidirectional"))
    )
    (net (code "166") (name "unconnected-(ATMEGA2560-PL7-Pad42)") (class "Default")
      (node (ref "ATMEGA2560") (pin "42") (pinfunction "PL7_42") (pintype "bidirectional"))
    )
    (net (code "167") (name "unconnected-(IC1B-+IN-Pad5)") (class "Default")
      (node (ref "IC1") (pin "5") (pinfunction "+IN_5") (pintype "input"))
    )
    (net (code "168") (name "unconnected-(IC1B--IN-Pad6)") (class "Default")
      (node (ref "IC1") (pin "6") (pinfunction "-IN_6") (pintype "input"))
    )
    (net (code "169") (name "unconnected-(IC1B-OUT-Pad7)") (class "Default")
      (node (ref "IC1") (pin "7") (pinfunction "OUT_7") (pintype "output"))
    )
    (net (code "170") (name "unconnected-(IC2-CBUS2-Pad13)") (class "Default")
      (node (ref "IC2") (pin "13") (pinfunction "CBUS2_13") (pintype "bidirectional"))
    )
    (net (code "171") (name "unconnected-(IC2-CBUS3-Pad14)") (class "Default")
      (node (ref "IC2") (pin "14") (pinfunction "CBUS3_14") (pintype "bidirectional"))
    )
    (net (code "172") (name "unconnected-(IC2-CBUS4-Pad12)") (class "Default")
      (node (ref "IC2") (pin "12") (pinfunction "CBUS4_12") (pintype "bidirectional"))
    )
    (net (code "173") (name "unconnected-(IC2-OSCI-Pad27)") (class "Default")
      (node (ref "IC2") (pin "27") (pinfunction "OSCI_27") (pintype "input"))
    )
    (net (code "174") (name "unconnected-(IC2-OSCO-Pad28)") (class "Default")
      (node (ref "IC2") (pin "28") (pinfunction "OSCO_28") (pintype "output"))
    )
    (net (code "175") (name "unconnected-(IC2-~{CTS}-Pad11)") (class "Default")
      (node (ref "IC2") (pin "11") (pinfunction "~{CTS}_11") (pintype "input"))
    )
    (net (code "176") (name "unconnected-(IC2-~{DCD}-Pad10)") (class "Default")
      (node (ref "IC2") (pin "10") (pinfunction "~{DCD}_10") (pintype "input"))
    )
    (net (code "177") (name "unconnected-(IC2-~{DSR}-Pad9)") (class "Default")
      (node (ref "IC2") (pin "9") (pinfunction "~{DSR}_9") (pintype "input"))
    )
    (net (code "178") (name "unconnected-(IC2-~{RI}-Pad6)") (class "Default")
      (node (ref "IC2") (pin "6") (pinfunction "~{RI}_6") (pintype "input"))
    )
    (net (code "179") (name "unconnected-(IC2-~{RTS}-Pad3)") (class "Default")
      (node (ref "IC2") (pin "3") (pinfunction "~{RTS}_3") (pintype "output"))
    )
    (net (code "180") (name "unconnected-(IC3-ON-Pad5)") (class "Default")
      (node (ref "IC3") (pin "5") (pinfunction "ON_5") (pintype "passive"))
    )
    (net (code "181") (name "unconnected-(IC3-ON{slash}STR-Pad6)") (class "Default")
      (node (ref "IC3") (pin "6") (pinfunction "ON/STR_6") (pintype "passive"))
    )
    (net (code "182") (name "unconnected-(K1-PadO)") (class "Default")
      (node (ref "K1") (pin "O") (pinfunction "O_O") (pintype "passive"))
    )
  )
)
